# FPGA_Top.net
KiCad netlist of a schematic drawn in Altium Designer
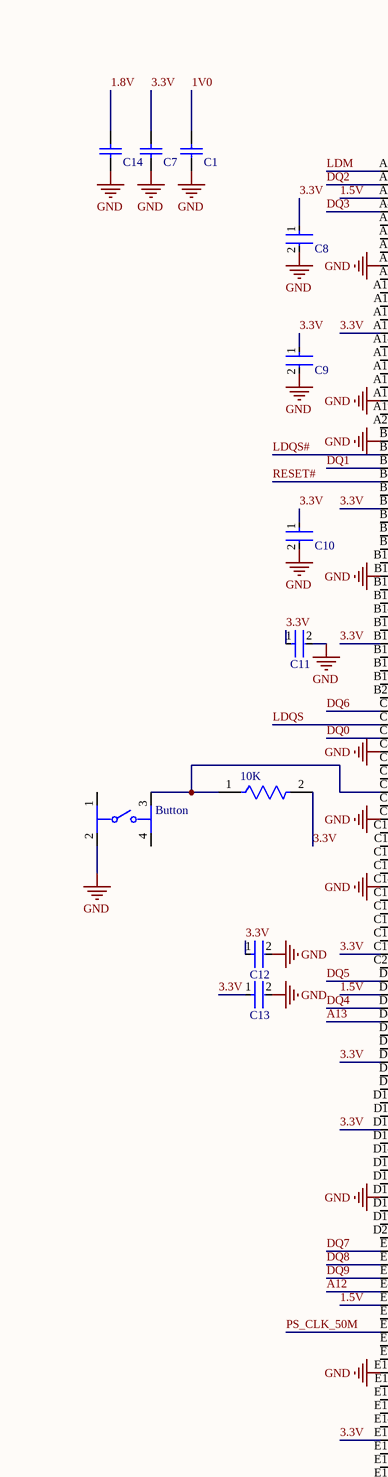
[diagram p0: FPGA_Top.SchDoc, top left]
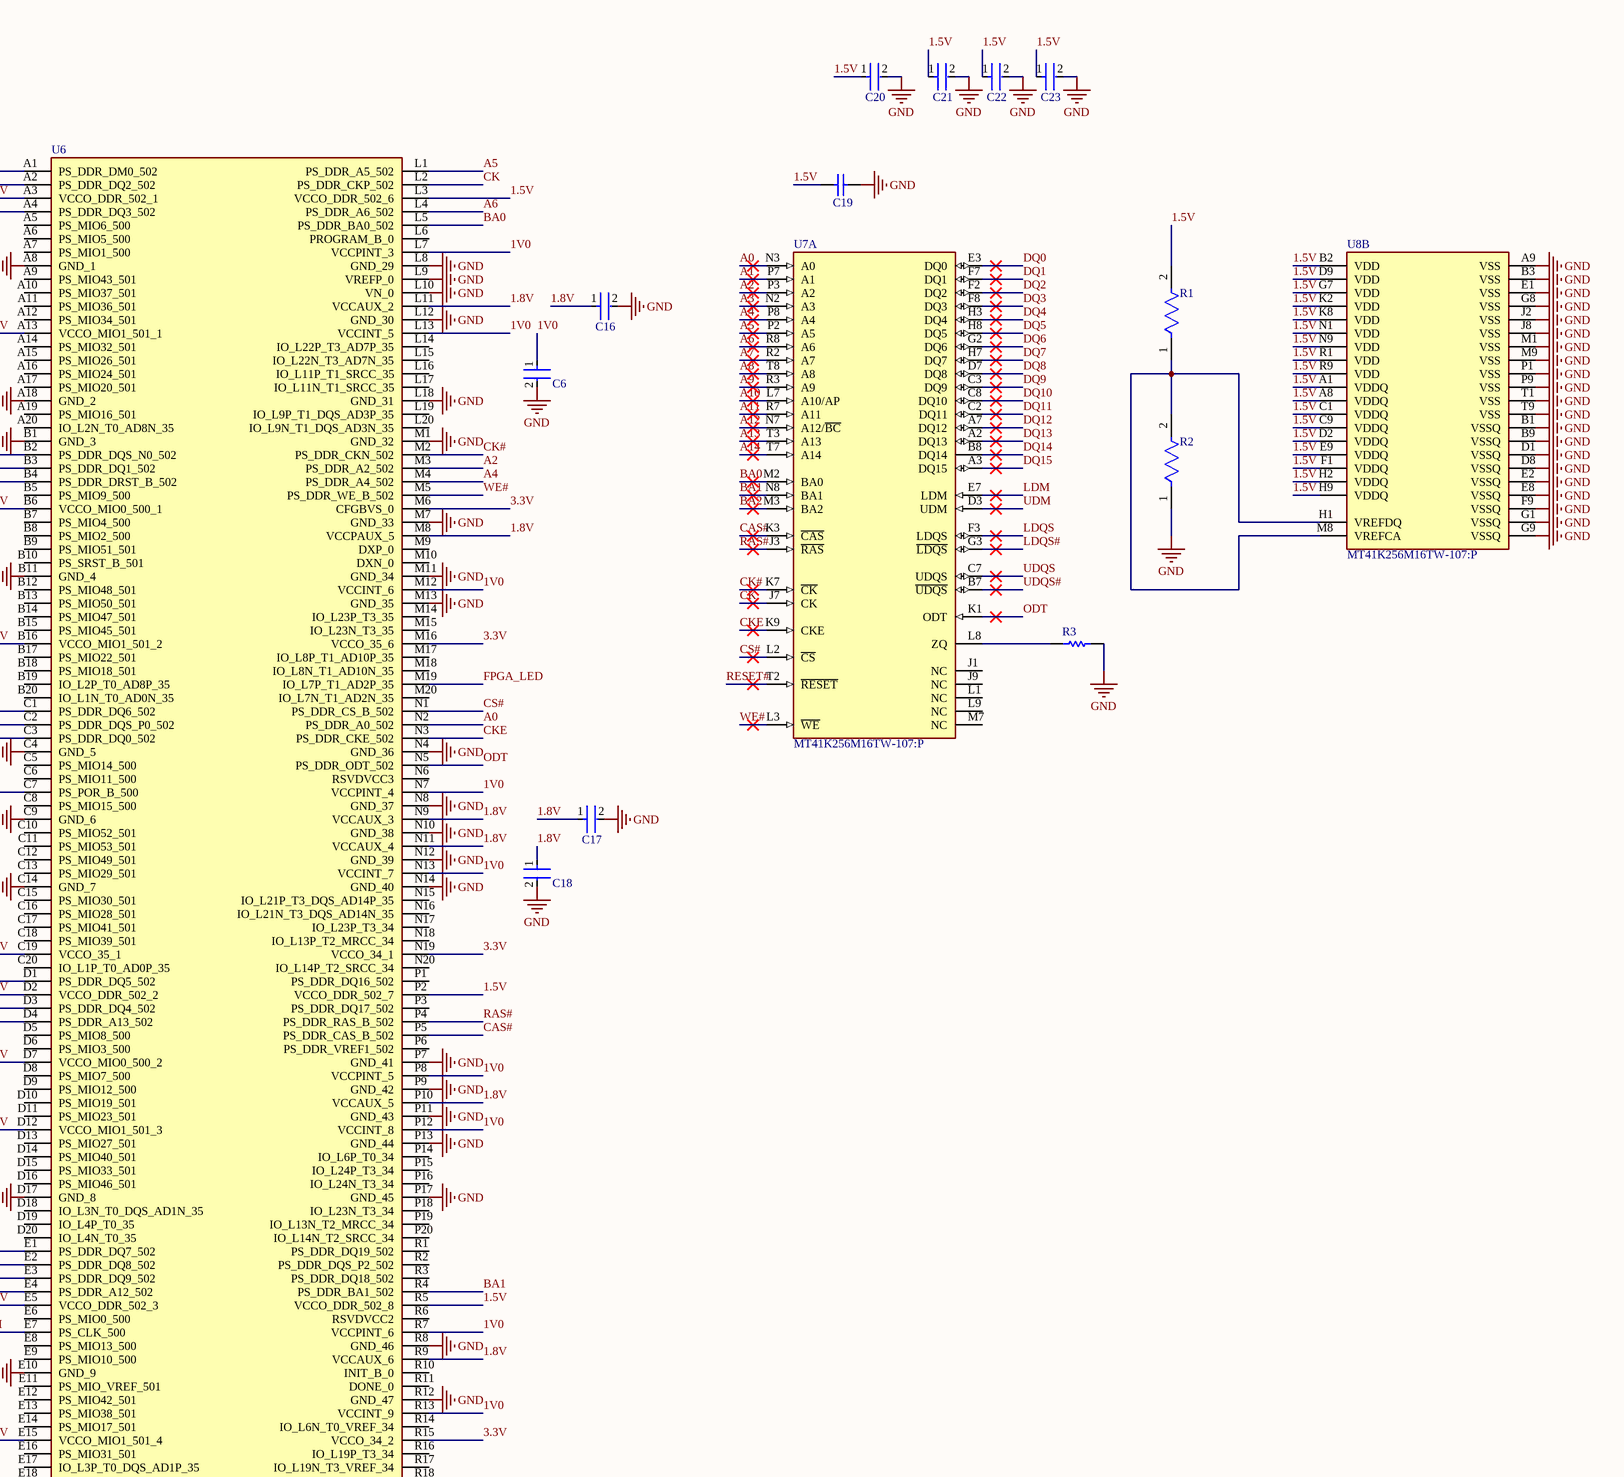
[diagram p1: FPGA_Top.SchDoc, top right]
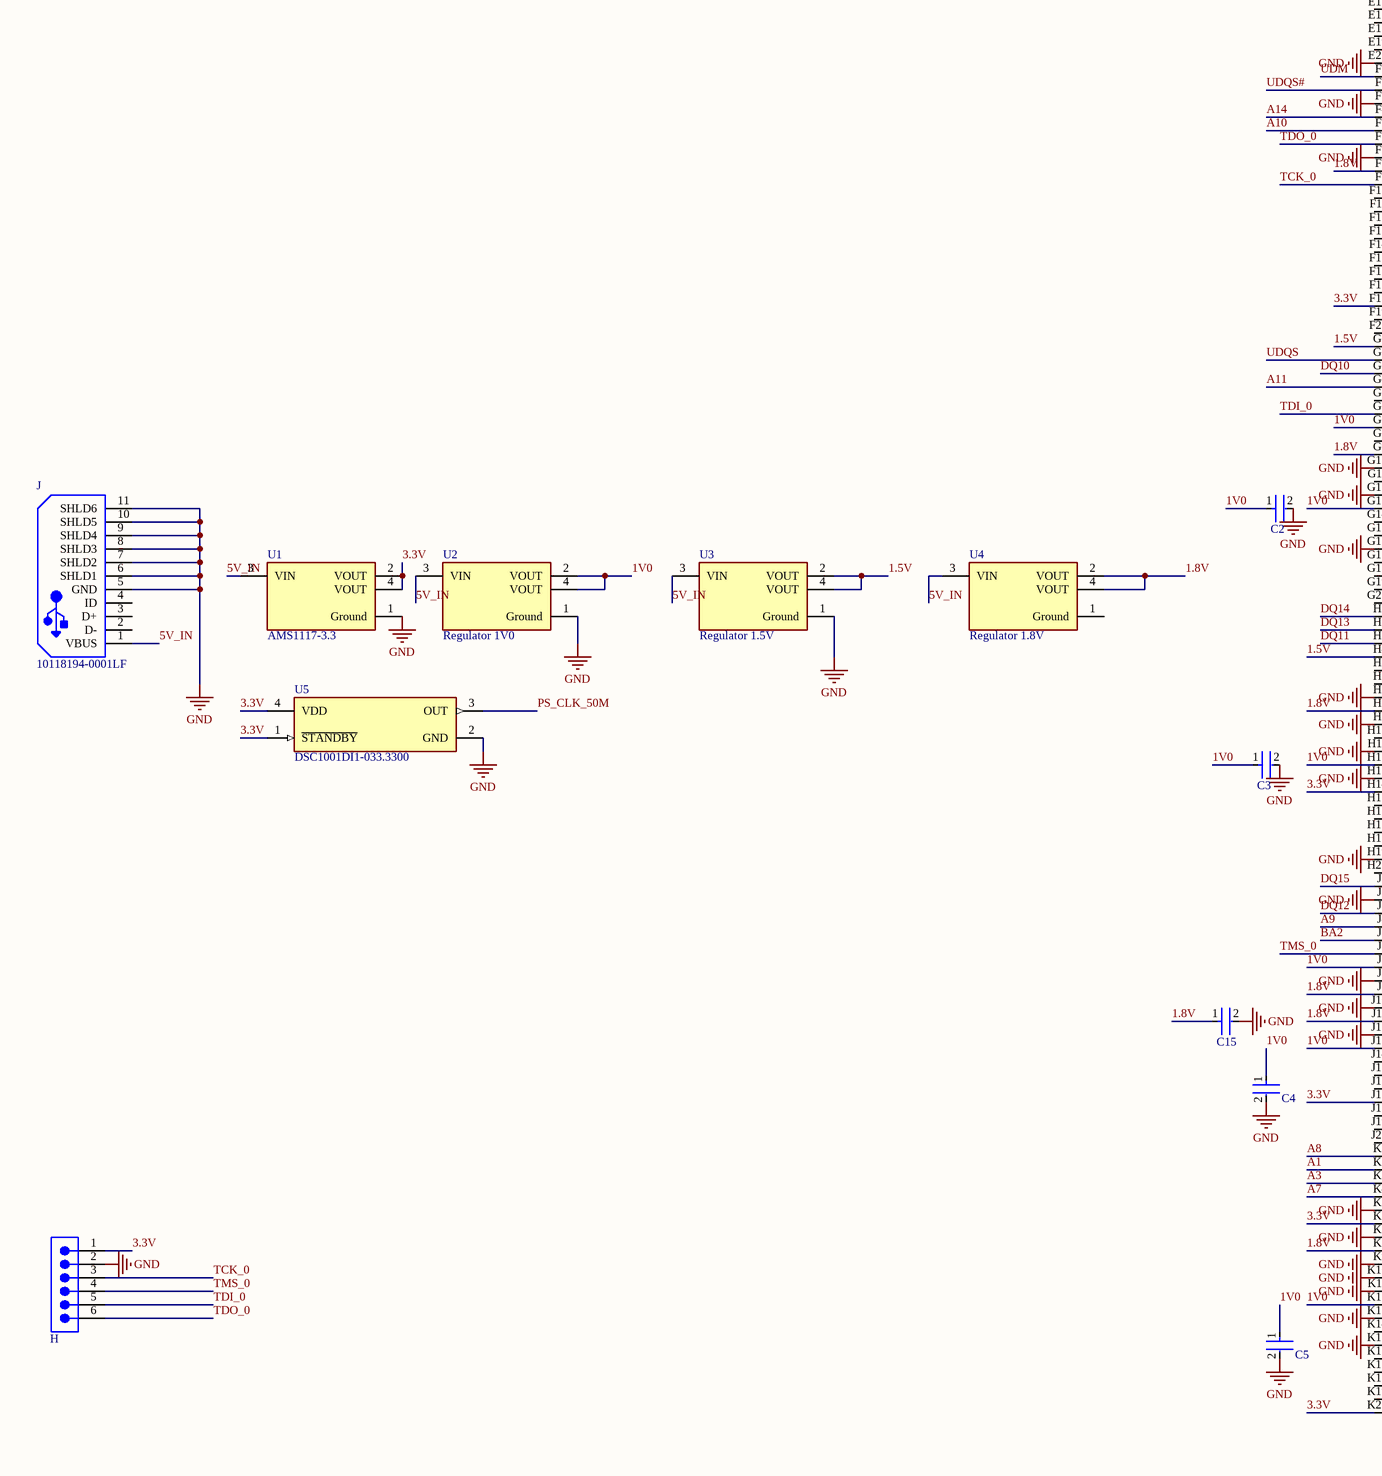
[diagram p2: FPGA_Top.SchDoc, bottom left]
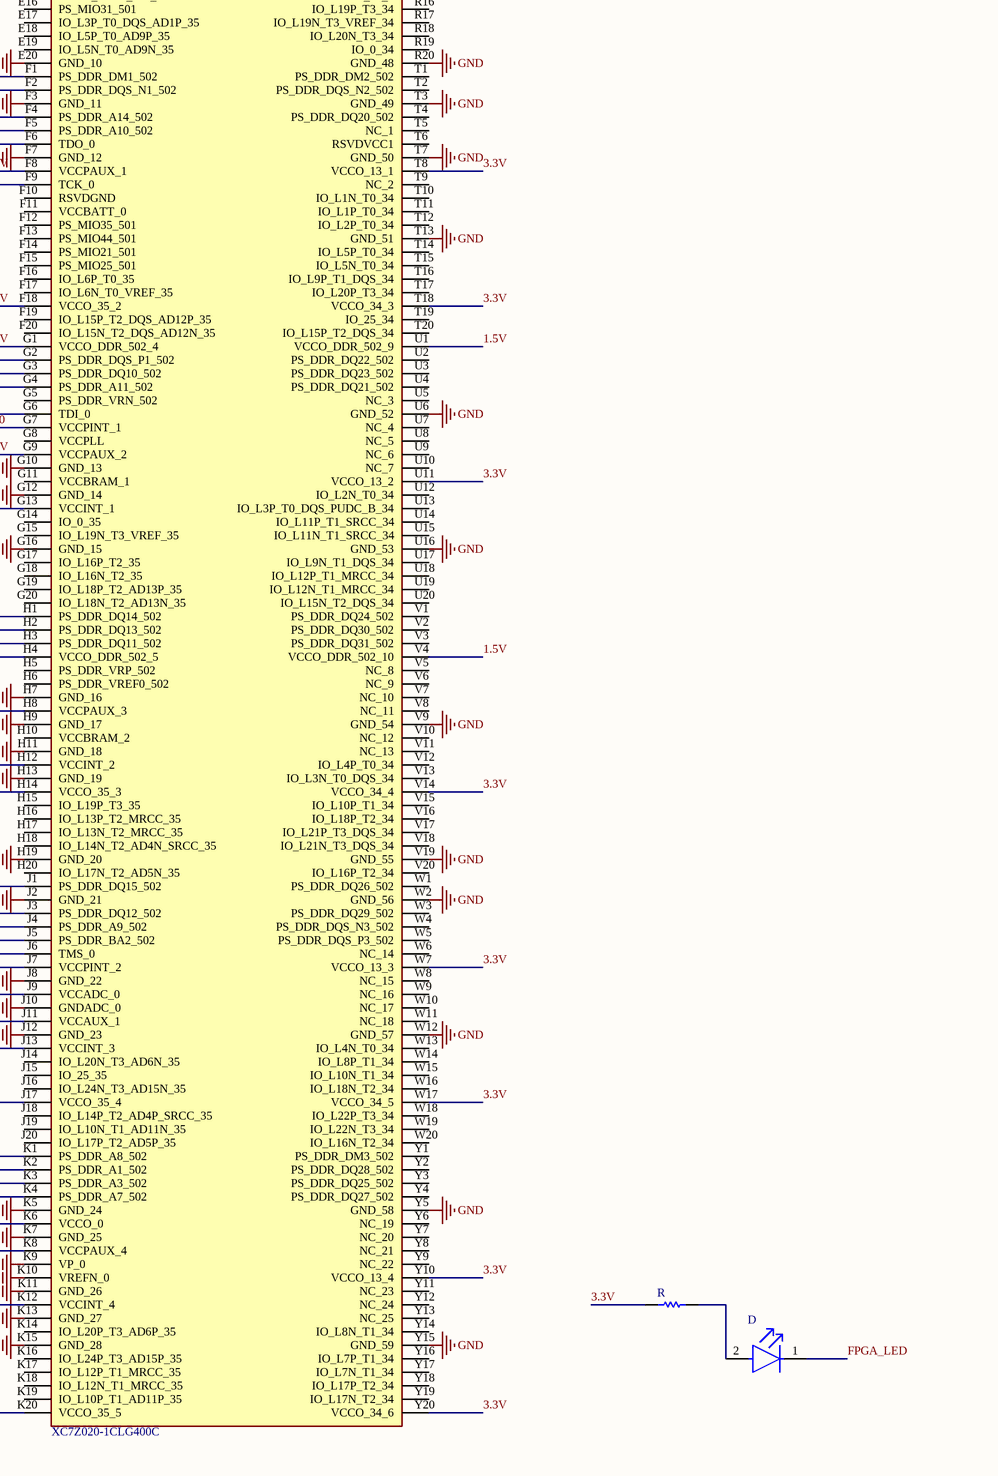
[diagram p3: FPGA_Top.SchDoc, bottom right]

(export (version "E")
  (design (tool "Eeschema 10.0.6"))
  (components
    (comp (ref "10K")
      (value "RC0402JR-0710KL")
      (footprint "FP-RC0402-0_4-IPC_C")
      (description "RES 10K OHM 5% 1/16W 0402")
      (fields (field (name "TOLERANCE") "5%"))
      (libsource (lib "Altium Content Vault") (part "1029c3af85768c4190bb7ad29bc67b5"))
    )
    (comp (ref "Button")
      (value "4-1437565-1")
      (footprint "FP-4-1437565-1-MFG")
      (description "SWITCH TACTILE SPST-NO 0.05A 24V")
      (fields
        (field (name "MANUFACTURER") "TE Connectivity")
        (field (name "OCTOPART") "https://octopart.com/fsm4jsma-te+connectivity-55488004")
      )
      (libsource (lib "Altium Content Vault") (part "b8895f3f4cefb76e1819d2863dba89b"))
    )
    (comp (ref "C1")
      (value "CL10A475KQ8NNNC")
      (footprint "CAPC1608X90X30LL10T20")
      (description "Chip Capacitor, 4.7 uF, +/- 10%, 6.3 V, -55 to 85 degC, 0603 (1608 Metric), RoHS, Tape and Reel")
      (fields (field (name "MANUFACTURER") "Samsung Electro-Mechanics"))
      (libsource (lib "Altium Content Vault") (part "CAP-NP-2"))
    )
    (comp (ref "C2")
      (value "CC0402KRX7R9BB104")
      (footprint "FP-CC0402-MFG")
      (description "CAP CER 0.1UF 50V X7R 0402")
      (fields
        (field (name "MANUFACTURER") "YAGEO")
        (field (name "OCTOPART") "https://octopart.com/cc0402krx7r9bb104-yageo-56536067")
      )
      (libsource (lib "Altium Content Vault") (part "11868f565c42a9108669ba33697ecf6"))
    )
    (comp (ref "C3")
      (value "CC0402KRX7R9BB104")
      (footprint "FP-CC0402-MFG")
      (description "CAP CER 0.1UF 50V X7R 0402")
      (fields
        (field (name "MANUFACTURER") "YAGEO")
        (field (name "OCTOPART") "https://octopart.com/cc0402krx7r9bb104-yageo-56536067")
      )
      (libsource (lib "Altium Content Vault") (part "11868f565c42a9108669ba33697ecf6"))
    )
    (comp (ref "C4")
      (value "CC0402KRX7R9BB104")
      (footprint "FP-CC0402-MFG")
      (description "CAP CER 0.1UF 50V X7R 0402")
      (fields
        (field (name "MANUFACTURER") "YAGEO")
        (field (name "OCTOPART") "https://octopart.com/cc0402krx7r9bb104-yageo-56536067")
      )
      (libsource (lib "Altium Content Vault") (part "11868f565c42a9108669ba33697ecf6"))
    )
    (comp (ref "C5")
      (value "CC0402KRX7R9BB104")
      (footprint "FP-CC0402-MFG")
      (description "CAP CER 0.1UF 50V X7R 0402")
      (fields
        (field (name "MANUFACTURER") "YAGEO")
        (field (name "OCTOPART") "https://octopart.com/cc0402krx7r9bb104-yageo-56536067")
      )
      (libsource (lib "Altium Content Vault") (part "11868f565c42a9108669ba33697ecf6"))
    )
    (comp (ref "C6")
      (value "CC0402KRX7R9BB104")
      (footprint "FP-CC0402-MFG")
      (description "CAP CER 0.1UF 50V X7R 0402")
      (fields
        (field (name "MANUFACTURER") "YAGEO")
        (field (name "OCTOPART") "https://octopart.com/cc0402krx7r9bb104-yageo-56536067")
      )
      (libsource (lib "Altium Content Vault") (part "11868f565c42a9108669ba33697ecf6"))
    )
    (comp (ref "C7")
      (value "CL10A475KQ8NNNC")
      (footprint "CAPC1608X90X30LL10T20")
      (description "Chip Capacitor, 4.7 uF, +/- 10%, 6.3 V, -55 to 85 degC, 0603 (1608 Metric), RoHS, Tape and Reel")
      (fields (field (name "MANUFACTURER") "Samsung Electro-Mechanics"))
      (libsource (lib "Altium Content Vault") (part "CAP-NP-2"))
    )
    (comp (ref "C8")
      (value "CC0402KRX7R9BB104")
      (footprint "FP-CC0402-MFG")
      (description "CAP CER 0.1UF 50V X7R 0402")
      (fields
        (field (name "MANUFACTURER") "YAGEO")
        (field (name "OCTOPART") "https://octopart.com/cc0402krx7r9bb104-yageo-56536067")
      )
      (libsource (lib "Altium Content Vault") (part "11868f565c42a9108669ba33697ecf6"))
    )
    (comp (ref "C9")
      (value "CC0402KRX7R9BB104")
      (footprint "FP-CC0402-MFG")
      (description "CAP CER 0.1UF 50V X7R 0402")
      (fields
        (field (name "MANUFACTURER") "YAGEO")
        (field (name "OCTOPART") "https://octopart.com/cc0402krx7r9bb104-yageo-56536067")
      )
      (libsource (lib "Altium Content Vault") (part "11868f565c42a9108669ba33697ecf6"))
    )
    (comp (ref "C10")
      (value "CC0402KRX7R9BB104")
      (footprint "FP-CC0402-MFG")
      (description "CAP CER 0.1UF 50V X7R 0402")
      (fields
        (field (name "MANUFACTURER") "YAGEO")
        (field (name "OCTOPART") "https://octopart.com/cc0402krx7r9bb104-yageo-56536067")
      )
      (libsource (lib "Altium Content Vault") (part "11868f565c42a9108669ba33697ecf6"))
    )
    (comp (ref "C11")
      (value "CC0402KRX7R9BB104")
      (footprint "FP-CC0402-MFG")
      (description "CAP CER 0.1UF 50V X7R 0402")
      (fields
        (field (name "MANUFACTURER") "YAGEO")
        (field (name "OCTOPART") "https://octopart.com/cc0402krx7r9bb104-yageo-56536067")
      )
      (libsource (lib "Altium Content Vault") (part "11868f565c42a9108669ba33697ecf6"))
    )
    (comp (ref "C12")
      (value "CC0402KRX7R9BB104")
      (footprint "FP-CC0402-MFG")
      (description "CAP CER 0.1UF 50V X7R 0402")
      (fields
        (field (name "MANUFACTURER") "YAGEO")
        (field (name "OCTOPART") "https://octopart.com/cc0402krx7r9bb104-yageo-56536067")
      )
      (libsource (lib "Altium Content Vault") (part "11868f565c42a9108669ba33697ecf6"))
    )
    (comp (ref "C13")
      (value "CC0402KRX7R9BB104")
      (footprint "FP-CC0402-MFG")
      (description "CAP CER 0.1UF 50V X7R 0402")
      (fields
        (field (name "MANUFACTURER") "YAGEO")
        (field (name "OCTOPART") "https://octopart.com/cc0402krx7r9bb104-yageo-56536067")
      )
      (libsource (lib "Altium Content Vault") (part "11868f565c42a9108669ba33697ecf6"))
    )
    (comp (ref "C14")
      (value "CL10A475KQ8NNNC")
      (footprint "CAPC1608X90X30LL10T20")
      (description "Chip Capacitor, 4.7 uF, +/- 10%, 6.3 V, -55 to 85 degC, 0603 (1608 Metric), RoHS, Tape and Reel")
      (fields (field (name "MANUFACTURER") "Samsung Electro-Mechanics"))
      (libsource (lib "Altium Content Vault") (part "CAP-NP-2"))
    )
    (comp (ref "C15")
      (value "CC0402KRX7R9BB104")
      (footprint "FP-CC0402-MFG")
      (description "CAP CER 0.1UF 50V X7R 0402")
      (fields
        (field (name "MANUFACTURER") "YAGEO")
        (field (name "OCTOPART") "https://octopart.com/cc0402krx7r9bb104-yageo-56536067")
      )
      (libsource (lib "Altium Content Vault") (part "11868f565c42a9108669ba33697ecf6"))
    )
    (comp (ref "C16")
      (value "CC0402KRX7R9BB104")
      (footprint "FP-CC0402-MFG")
      (description "CAP CER 0.1UF 50V X7R 0402")
      (fields
        (field (name "MANUFACTURER") "YAGEO")
        (field (name "OCTOPART") "https://octopart.com/cc0402krx7r9bb104-yageo-56536067")
      )
      (libsource (lib "Altium Content Vault") (part "11868f565c42a9108669ba33697ecf6"))
    )
    (comp (ref "C17")
      (value "CC0402KRX7R9BB104")
      (footprint "FP-CC0402-MFG")
      (description "CAP CER 0.1UF 50V X7R 0402")
      (fields
        (field (name "MANUFACTURER") "YAGEO")
        (field (name "OCTOPART") "https://octopart.com/cc0402krx7r9bb104-yageo-56536067")
      )
      (libsource (lib "Altium Content Vault") (part "11868f565c42a9108669ba33697ecf6"))
    )
    (comp (ref "C18")
      (value "CC0402KRX7R9BB104")
      (footprint "FP-CC0402-MFG")
      (description "CAP CER 0.1UF 50V X7R 0402")
      (fields
        (field (name "MANUFACTURER") "YAGEO")
        (field (name "OCTOPART") "https://octopart.com/cc0402krx7r9bb104-yageo-56536067")
      )
      (libsource (lib "Altium Content Vault") (part "11868f565c42a9108669ba33697ecf6"))
    )
    (comp (ref "C19")
      (value "CL10A475KQ8NNNC")
      (footprint "CAPC1608X90X30LL10T20")
      (description "Chip Capacitor, 4.7 uF, +/- 10%, 6.3 V, -55 to 85 degC, 0603 (1608 Metric), RoHS, Tape and Reel")
      (fields (field (name "MANUFACTURER") "Samsung Electro-Mechanics"))
      (libsource (lib "Altium Content Vault") (part "CAP-NP-2"))
    )
    (comp (ref "C20")
      (value "CC0402KRX7R9BB104")
      (footprint "FP-CC0402-MFG")
      (description "CAP CER 0.1UF 50V X7R 0402")
      (fields
        (field (name "MANUFACTURER") "YAGEO")
        (field (name "OCTOPART") "https://octopart.com/cc0402krx7r9bb104-yageo-56536067")
      )
      (libsource (lib "Altium Content Vault") (part "11868f565c42a9108669ba33697ecf6"))
    )
    (comp (ref "C21")
      (value "CC0402KRX7R9BB104")
      (footprint "FP-CC0402-MFG")
      (description "CAP CER 0.1UF 50V X7R 0402")
      (fields
        (field (name "MANUFACTURER") "YAGEO")
        (field (name "OCTOPART") "https://octopart.com/cc0402krx7r9bb104-yageo-56536067")
      )
      (libsource (lib "Altium Content Vault") (part "11868f565c42a9108669ba33697ecf6"))
    )
    (comp (ref "C22")
      (value "CC0402KRX7R9BB104")
      (footprint "FP-CC0402-MFG")
      (description "CAP CER 0.1UF 50V X7R 0402")
      (fields
        (field (name "MANUFACTURER") "YAGEO")
        (field (name "OCTOPART") "https://octopart.com/cc0402krx7r9bb104-yageo-56536067")
      )
      (libsource (lib "Altium Content Vault") (part "11868f565c42a9108669ba33697ecf6"))
    )
    (comp (ref "C23")
      (value "CC0402KRX7R9BB104")
      (footprint "FP-CC0402-MFG")
      (description "CAP CER 0.1UF 50V X7R 0402")
      (fields
        (field (name "MANUFACTURER") "YAGEO")
        (field (name "OCTOPART") "https://octopart.com/cc0402krx7r9bb104-yageo-56536067")
      )
      (libsource (lib "Altium Content Vault") (part "11868f565c42a9108669ba33697ecf6"))
    )
    (comp (ref "D")
      (value "LTST-C190KRKT")
      (footprint "FP-LTST-C190KRKT-MFG")
      (description "LED RED CLEAR CHIP SMD")
      (libsource (lib "Altium Content Vault") (part "8706943c75ba83719d021d2fdc84c58"))
    )
    (comp (ref "H")
      (value "TSW-106-07-G-S")
      (footprint "SMTC-TSW-106-07-X-S")
      (description "0.025\" SQ Post Header, Through-hole, Vertical, -55 to 125 degC, 2.54 mm Pitch, 6-Pin, Male, RoHS")
      (fields (field (name "MANUFACTURER") "Samtec"))
      (libsource (lib "Altium Content Vault") (part "SMTC-TSW-106-X-X-S-X"))
    )
    (comp (ref "J")
      (value "10118194-0001LF")
      (footprint "FCI-10118194-0001LF-5_V")
      (description "Micro USB B Type Receptacle, 1.8 A, -55 to 85 degC, 5-Pin SMD, RoHS, Tape and Reel")
      (fields (field (name "MANUFACTURER") "Amphenol FCI"))
      (libsource (lib "Altium Content Vault") (part "USB-5-6SHLD"))
    )
    (comp (ref "R")
      (value "RC0402JR-07330RL")
      (footprint "RESC1005X40X25NL05T10")
      (fields (field (name "MANUFACTURER") "Yageo / Phycomp"))
      (libsource (lib "Altium Content Vault") (part "RES"))
    )
    (comp (ref "R1")
      (value "RC0402FR-071KL")
      (footprint "FP-RC0402-0_4-IPC_A")
      (description "RES 1K OHM 1% 1/16W 0402")
      (fields (field (name "TOLERANCE") "1%"))
      (libsource (lib "Altium Content Vault") (part "1029c3af85768c4190bb7ad29bc67b5"))
    )
    (comp (ref "R2")
      (value "RC0402FR-071KL")
      (footprint "FP-RC0402-0_4-IPC_A")
      (description "RES 1K OHM 1% 1/16W 0402")
      (fields (field (name "TOLERANCE") "1%"))
      (libsource (lib "Altium Content Vault") (part "1029c3af85768c4190bb7ad29bc67b5"))
    )
    (comp (ref "R3")
      (value "240R 1% 0402(1005)")
      (footprint "RESC0402(1005)_L")
      (description "240R 0.063W 1% 0402 (1005 Metric)  SMD")
      (fields (field (name "POWER") "0.063 W") (field (name "TOLERANCE") "1 %"))
      (libsource (lib "Altium Content Vault") (part "RES"))
    )
    (comp (ref "U1")
      (value "AMS1117-3.3")
      (footprint "FP-AMS1117-IPC_C")
      (description "LDO Voltage Regulators 1A, 3.3V")
      (fields
        (field (name "OCTOPART") "https://octopart.com/ams1117-3.3-advanced+monolithic+systems-25899300")
        (field (name "MANUFACTURER") "Advanced Monolithic Systems")
      )
      (libsource (lib "Altium Content Vault") (part "8bdbb5f8e77002000e30dd2845d0354"))
    )
    (comp (ref "U2")
      (value "Regulator 1V0")
      (footprint "FP-AMS1117-IPC_C")
      (description "LDO Voltage Regulators 1A, 3.3V")
      (fields
        (field (name "MANUFACTURER PART NUMBER") "AMS1117-3.3")
        (field (name "OCTOPART") "https://octopart.com/ams1117-3.3-advanced+monolithic+systems-25899300")
      )
      (libsource (lib "Altium Content Vault") (part "8bdbb5f8e77002000e30dd2845d0354"))
    )
    (comp (ref "U3")
      (value "Regulator 1.5V")
      (footprint "FP-AMS1117-IPC_C")
      (description "LDO Voltage Regulators 1A, 3.3V")
      (fields
        (field (name "MANUFACTURER PART NUMBER") "AMS1117-3.3")
        (field (name "OCTOPART") "https://octopart.com/ams1117-3.3-advanced+monolithic+systems-25899300")
      )
      (libsource (lib "Altium Content Vault") (part "8bdbb5f8e77002000e30dd2845d0354"))
    )
    (comp (ref "U4")
      (value "Regulator 1.8V")
      (footprint "FP-AMS1117-IPC_C")
      (description "LDO Voltage Regulators 1A, 3.3V")
      (fields
        (field (name "MANUFACTURER PART NUMBER") "AMS1117-3.3")
        (field (name "OCTOPART") "https://octopart.com/ams1117-3.3-advanced+monolithic+systems-25899300")
      )
      (libsource (lib "Altium Content Vault") (part "8bdbb5f8e77002000e30dd2845d0354"))
    )
    (comp (ref "U5")
      (value "DSC1001DI1-033.3300")
      (footprint "FP-CDFN2520-4LD-PL-1-MFG")
      (description "MEMS OSC XO 33.3300MHZ CMOS SMD")
      (libsource (lib "Altium Content Vault") (part "8720c5899389794f50cb41edc4e4c8a"))
    )
    (comp (ref "U6")
      (value "XC7Z020-1CLG400C")
      (footprint "BGA400C80P20X20_1700X1700X160")
      (description "Zynq-7000 All Programmable SoC, BGA-400")
      (fields (field (name "MOUSER PART NUMBER") "217-XC7Z020-1CLG400C"))
      (libsource (lib "Altium 365 Cloud") (part "XC7Z020-1CLG400C"))
    )
    (comp (ref "U7")
      (value "MT41K256M16TW-107:P")
      (footprint "FP-TW-IPC_C")
      (description "IC DRAM 4G PARALLEL 96FBGA")
      (fields
        (field (name "MANUFACTURER") "Micron")
        (field (name "OCTOPART") "https://octopart.com/mt41k256m16tw-107%3Ap-micron-66533852")
      )
      (libsource (lib "Altium Content Vault") (part "cdaccbdf9e98e5f2804aaab7a1ea706"))
    )
    (comp (ref "U8")
      (value "MT41K256M16TW-107:P")
      (footprint "FP-TW-IPC_C")
      (description "IC DRAM 4G PARALLEL 96FBGA")
      (fields
        (field (name "MANUFACTURER") "Micron")
        (field (name "OCTOPART") "https://octopart.com/mt41k256m16tw-107%3Ap-micron-66533852")
      )
      (libsource (lib "Altium Content Vault") (part "cdaccbdf9e98e5f2804aaab7a1ea706"))
    )
  )
  (nets
    (net (code "1") (name "/1.5V") (class "Default")
      (node (ref "C19") (pin "2") (pinfunction "2_2") (pintype "passive"))
      (node (ref "C20") (pin "1") (pinfunction "1_1") (pintype "passive"))
      (node (ref "C21") (pin "1") (pinfunction "1_1") (pintype "passive"))
      (node (ref "C22") (pin "1") (pinfunction "1_1") (pintype "passive"))
      (node (ref "C23") (pin "1") (pinfunction "1_1") (pintype "passive"))
      (node (ref "R1") (pin "2") (pinfunction "2_2") (pintype "passive"))
      (node (ref "U3") (pin "2") (pinfunction "VOUT_2") (pintype "passive"))
      (node (ref "U3") (pin "4") (pinfunction "VOUT_4") (pintype "passive"))
      (node (ref "U6") (pin "A3") (pinfunction "VCCO_DDR_502_1_A3") (pintype "passive"))
      (node (ref "U6") (pin "D2") (pinfunction "VCCO_DDR_502_2_D2") (pintype "passive"))
      (node (ref "U6") (pin "E5") (pinfunction "VCCO_DDR_502_3_E5") (pintype "passive"))
      (node (ref "U6") (pin "G1") (pinfunction "VCCO_DDR_502_4_G1") (pintype "passive"))
      (node (ref "U6") (pin "H4") (pinfunction "VCCO_DDR_502_5_H4") (pintype "passive"))
      (node (ref "U6") (pin "L3") (pinfunction "VCCO_DDR_502_6_L3") (pintype "passive"))
      (node (ref "U6") (pin "P2") (pinfunction "VCCO_DDR_502_7_P2") (pintype "passive"))
      (node (ref "U6") (pin "R5") (pinfunction "VCCO_DDR_502_8_R5") (pintype "passive"))
      (node (ref "U6") (pin "U1") (pinfunction "VCCO_DDR_502_9_U1") (pintype "passive"))
      (node (ref "U6") (pin "V4") (pinfunction "VCCO_DDR_502_10_V4") (pintype "passive"))
      (node (ref "U8") (pin "A1") (pinfunction "VDDQ_A1") (pintype "power_in"))
      (node (ref "U8") (pin "A8") (pinfunction "VDDQ_A8") (pintype "power_in"))
      (node (ref "U8") (pin "B2") (pinfunction "VDD_B2") (pintype "power_in"))
      (node (ref "U8") (pin "C1") (pinfunction "VDDQ_C1") (pintype "power_in"))
      (node (ref "U8") (pin "C9") (pinfunction "VDDQ_C9") (pintype "power_in"))
      (node (ref "U8") (pin "D2") (pinfunction "VDDQ_D2") (pintype "power_in"))
      (node (ref "U8") (pin "D9") (pinfunction "VDD_D9") (pintype "power_in"))
      (node (ref "U8") (pin "E9") (pinfunction "VDDQ_E9") (pintype "power_in"))
      (node (ref "U8") (pin "F1") (pinfunction "VDDQ_F1") (pintype "power_in"))
      (node (ref "U8") (pin "G7") (pinfunction "VDD_G7") (pintype "power_in"))
      (node (ref "U8") (pin "H2") (pinfunction "VDDQ_H2") (pintype "power_in"))
      (node (ref "U8") (pin "H9") (pinfunction "VDDQ_H9") (pintype "power_in"))
      (node (ref "U8") (pin "K2") (pinfunction "VDD_K2") (pintype "power_in"))
      (node (ref "U8") (pin "K8") (pinfunction "VDD_K8") (pintype "power_in"))
      (node (ref "U8") (pin "N1") (pinfunction "VDD_N1") (pintype "power_in"))
      (node (ref "U8") (pin "N9") (pinfunction "VDD_N9") (pintype "power_in"))
      (node (ref "U8") (pin "R1") (pinfunction "VDD_R1") (pintype "power_in"))
      (node (ref "U8") (pin "R9") (pinfunction "VDD_R9") (pintype "power_in"))
    )
    (net (code "2") (name "/1.8V") (class "Default")
      (node (ref "C14") (pin "2") (pinfunction "2_2") (pintype "passive"))
      (node (ref "C15") (pin "1") (pinfunction "1_1") (pintype "passive"))
      (node (ref "C16") (pin "1") (pinfunction "1_1") (pintype "passive"))
      (node (ref "C17") (pin "1") (pinfunction "1_1") (pintype "passive"))
      (node (ref "C18") (pin "1") (pinfunction "1_1") (pintype "passive"))
      (node (ref "U4") (pin "2") (pinfunction "VOUT_2") (pintype "passive"))
      (node (ref "U4") (pin "4") (pinfunction "VOUT_4") (pintype "passive"))
      (node (ref "U6") (pin "F8") (pinfunction "VCCPAUX_1_F8") (pintype "passive"))
      (node (ref "U6") (pin "G9") (pinfunction "VCCPAUX_2_G9") (pintype "passive"))
      (node (ref "U6") (pin "H8") (pinfunction "VCCPAUX_3_H8") (pintype "passive"))
      (node (ref "U6") (pin "J11") (pinfunction "VCCAUX_1_J11") (pintype "passive"))
      (node (ref "U6") (pin "J9") (pinfunction "VCCADC_0_J9") (pintype "passive"))
      (node (ref "U6") (pin "K8") (pinfunction "VCCPAUX_4_K8") (pintype "passive"))
      (node (ref "U6") (pin "L11") (pinfunction "VCCAUX_2_L11") (pintype "passive"))
      (node (ref "U6") (pin "M8") (pinfunction "VCCPAUX_5_M8") (pintype "passive"))
      (node (ref "U6") (pin "N11") (pinfunction "VCCAUX_4_N11") (pintype "passive"))
      (node (ref "U6") (pin "N9") (pinfunction "VCCAUX_3_N9") (pintype "passive"))
      (node (ref "U6") (pin "P10") (pinfunction "VCCAUX_5_P10") (pintype "passive"))
      (node (ref "U6") (pin "R9") (pinfunction "VCCAUX_6_R9") (pintype "passive"))
    )
    (net (code "3") (name "/1V0") (class "Default")
      (node (ref "C1") (pin "2") (pinfunction "2_2") (pintype "passive"))
      (node (ref "C2") (pin "1") (pinfunction "1_1") (pintype "passive"))
      (node (ref "C3") (pin "1") (pinfunction "1_1") (pintype "passive"))
      (node (ref "C4") (pin "1") (pinfunction "1_1") (pintype "passive"))
      (node (ref "C5") (pin "1") (pinfunction "1_1") (pintype "passive"))
      (node (ref "C6") (pin "1") (pinfunction "1_1") (pintype "passive"))
      (node (ref "U2") (pin "2") (pinfunction "VOUT_2") (pintype "passive"))
      (node (ref "U2") (pin "4") (pinfunction "VOUT_4") (pintype "passive"))
      (node (ref "U6") (pin "G13") (pinfunction "VCCINT_1_G13") (pintype "passive"))
      (node (ref "U6") (pin "G7") (pinfunction "VCCPINT_1_G7") (pintype "passive"))
      (node (ref "U6") (pin "H12") (pinfunction "VCCINT_2_H12") (pintype "passive"))
      (node (ref "U6") (pin "J13") (pinfunction "VCCINT_3_J13") (pintype "passive"))
      (node (ref "U6") (pin "J7") (pinfunction "VCCPINT_2_J7") (pintype "passive"))
      (node (ref "U6") (pin "K12") (pinfunction "VCCINT_4_K12") (pintype "passive"))
      (node (ref "U6") (pin "L13") (pinfunction "VCCINT_5_L13") (pintype "passive"))
      (node (ref "U6") (pin "L7") (pinfunction "VCCPINT_3_L7") (pintype "passive"))
      (node (ref "U6") (pin "M12") (pinfunction "VCCINT_6_M12") (pintype "passive"))
      (node (ref "U6") (pin "N13") (pinfunction "VCCINT_7_N13") (pintype "passive"))
      (node (ref "U6") (pin "N7") (pinfunction "VCCPINT_4_N7") (pintype "passive"))
      (node (ref "U6") (pin "P12") (pinfunction "VCCINT_8_P12") (pintype "passive"))
      (node (ref "U6") (pin "P8") (pinfunction "VCCPINT_5_P8") (pintype "passive"))
      (node (ref "U6") (pin "R13") (pinfunction "VCCINT_9_R13") (pintype "passive"))
      (node (ref "U6") (pin "R7") (pinfunction "VCCPINT_6_R7") (pintype "passive"))
    )
    (net (code "4") (name "/3.3V") (class "Default")
      (node (ref "10K") (pin "2") (pinfunction "2_2") (pintype "passive"))
      (node (ref "C10") (pin "1") (pinfunction "1_1") (pintype "passive"))
      (node (ref "C11") (pin "1") (pinfunction "1_1") (pintype "passive"))
      (node (ref "C12") (pin "1") (pinfunction "1_1") (pintype "passive"))
      (node (ref "C13") (pin "1") (pinfunction "1_1") (pintype "passive"))
      (node (ref "C7") (pin "2") (pinfunction "2_2") (pintype "passive"))
      (node (ref "C8") (pin "1") (pinfunction "1_1") (pintype "passive"))
      (node (ref "C9") (pin "1") (pinfunction "1_1") (pintype "passive"))
      (node (ref "H") (pin "1") (pinfunction "1_1") (pintype "passive"))
      (node (ref "R") (pin "1") (pinfunction "1_1") (pintype "passive"))
      (node (ref "U1") (pin "2") (pinfunction "VOUT_2") (pintype "passive"))
      (node (ref "U1") (pin "4") (pinfunction "VOUT_4") (pintype "passive"))
      (node (ref "U5") (pin "1") (pinfunction "~{STANDBY}_1") (pintype "input"))
      (node (ref "U5") (pin "4") (pinfunction "VDD_4") (pintype "power_in"))
      (node (ref "U6") (pin "A13") (pinfunction "VCCO_MIO1_501_1_A13") (pintype "passive"))
      (node (ref "U6") (pin "B16") (pinfunction "VCCO_MIO1_501_2_B16") (pintype "passive"))
      (node (ref "U6") (pin "B6") (pinfunction "VCCO_MIO0_500_1_B6") (pintype "passive"))
      (node (ref "U6") (pin "C19") (pinfunction "VCCO_35_1_C19") (pintype "passive"))
      (node (ref "U6") (pin "D12") (pinfunction "VCCO_MIO1_501_3_D12") (pintype "passive"))
      (node (ref "U6") (pin "D7") (pinfunction "VCCO_MIO0_500_2_D7") (pintype "passive"))
      (node (ref "U6") (pin "E15") (pinfunction "VCCO_MIO1_501_4_E15") (pintype "passive"))
      (node (ref "U6") (pin "F18") (pinfunction "VCCO_35_2_F18") (pintype "passive"))
      (node (ref "U6") (pin "H14") (pinfunction "VCCO_35_3_H14") (pintype "passive"))
      (node (ref "U6") (pin "J17") (pinfunction "VCCO_35_4_J17") (pintype "passive"))
      (node (ref "U6") (pin "K20") (pinfunction "VCCO_35_5_K20") (pintype "passive"))
      (node (ref "U6") (pin "K6") (pinfunction "VCCO_0_K6") (pintype "passive"))
      (node (ref "U6") (pin "M16") (pinfunction "VCCO_35_6_M16") (pintype "passive"))
      (node (ref "U6") (pin "M6") (pinfunction "CFGBVS_0_M6") (pintype "passive"))
      (node (ref "U6") (pin "N19") (pinfunction "VCCO_34_1_N19") (pintype "passive"))
      (node (ref "U6") (pin "R15") (pinfunction "VCCO_34_2_R15") (pintype "passive"))
      (node (ref "U6") (pin "T18") (pinfunction "VCCO_34_3_T18") (pintype "passive"))
      (node (ref "U6") (pin "T8") (pinfunction "VCCO_13_1_T8") (pintype "passive"))
      (node (ref "U6") (pin "U11") (pinfunction "VCCO_13_2_U11") (pintype "passive"))
      (node (ref "U6") (pin "V14") (pinfunction "VCCO_34_4_V14") (pintype "passive"))
      (node (ref "U6") (pin "W17") (pinfunction "VCCO_34_5_W17") (pintype "passive"))
      (node (ref "U6") (pin "W7") (pinfunction "VCCO_13_3_W7") (pintype "passive"))
      (node (ref "U6") (pin "Y10") (pinfunction "VCCO_13_4_Y10") (pintype "passive"))
      (node (ref "U6") (pin "Y20") (pinfunction "VCCO_34_6_Y20") (pintype "passive"))
    )
    (net (code "5") (name "/5V_IN") (class "Default")
      (node (ref "J") (pin "1") (pinfunction "VBUS_1") (pintype "passive"))
      (node (ref "U1") (pin "3") (pinfunction "VIN_3") (pintype "power_in"))
      (node (ref "U2") (pin "3") (pinfunction "VIN_3") (pintype "power_in"))
      (node (ref "U3") (pin "3") (pinfunction "VIN_3") (pintype "power_in"))
      (node (ref "U4") (pin "3") (pinfunction "VIN_3") (pintype "power_in"))
    )
    (net (code "6") (name "/A0") (class "Default")
      (node (ref "U6") (pin "N2") (pinfunction "PS_DDR_A0_502_N2") (pintype "passive"))
      (node (ref "U7") (pin "N3") (pinfunction "A0_N3") (pintype "input"))
    )
    (net (code "7") (name "/A1") (class "Default")
      (node (ref "U6") (pin "K2") (pinfunction "PS_DDR_A1_502_K2") (pintype "passive"))
      (node (ref "U7") (pin "P7") (pinfunction "A1_P7") (pintype "input"))
    )
    (net (code "8") (name "/A2") (class "Default")
      (node (ref "U6") (pin "M3") (pinfunction "PS_DDR_A2_502_M3") (pintype "passive"))
      (node (ref "U7") (pin "P3") (pinfunction "A2_P3") (pintype "input"))
    )
    (net (code "9") (name "/A3") (class "Default")
      (node (ref "U6") (pin "K3") (pinfunction "PS_DDR_A3_502_K3") (pintype "passive"))
      (node (ref "U7") (pin "N2") (pinfunction "A3_N2") (pintype "input"))
    )
    (net (code "10") (name "/A4") (class "Default")
      (node (ref "U6") (pin "M4") (pinfunction "PS_DDR_A4_502_M4") (pintype "passive"))
      (node (ref "U7") (pin "P8") (pinfunction "A4_P8") (pintype "input"))
    )
    (net (code "11") (name "/A5") (class "Default")
      (node (ref "U6") (pin "L1") (pinfunction "PS_DDR_A5_502_L1") (pintype "passive"))
      (node (ref "U7") (pin "P2") (pinfunction "A5_P2") (pintype "input"))
    )
    (net (code "12") (name "/A6") (class "Default")
      (node (ref "U6") (pin "L4") (pinfunction "PS_DDR_A6_502_L4") (pintype "passive"))
      (node (ref "U7") (pin "R8") (pinfunction "A6_R8") (pintype "input"))
    )
    (net (code "13") (name "/A7") (class "Default")
      (node (ref "U6") (pin "K4") (pinfunction "PS_DDR_A7_502_K4") (pintype "passive"))
      (node (ref "U7") (pin "R2") (pinfunction "A7_R2") (pintype "input"))
    )
    (net (code "14") (name "/A8") (class "Default")
      (node (ref "U6") (pin "K1") (pinfunction "PS_DDR_A8_502_K1") (pintype "passive"))
      (node (ref "U7") (pin "T8") (pinfunction "A8_T8") (pintype "input"))
    )
    (net (code "15") (name "/A9") (class "Default")
      (node (ref "U6") (pin "J4") (pinfunction "PS_DDR_A9_502_J4") (pintype "passive"))
      (node (ref "U7") (pin "R3") (pinfunction "A9_R3") (pintype "input"))
    )
    (net (code "16") (name "/A10") (class "Default")
      (node (ref "U6") (pin "F5") (pinfunction "PS_DDR_A10_502_F5") (pintype "passive"))
      (node (ref "U7") (pin "L7") (pinfunction "A10/AP_L7") (pintype "input"))
    )
    (net (code "17") (name "/A11") (class "Default")
      (node (ref "U6") (pin "G4") (pinfunction "PS_DDR_A11_502_G4") (pintype "passive"))
      (node (ref "U7") (pin "R7") (pinfunction "A11_R7") (pintype "input"))
    )
    (net (code "18") (name "/A12") (class "Default")
      (node (ref "U6") (pin "E4") (pinfunction "PS_DDR_A12_502_E4") (pintype "passive"))
      (node (ref "U7") (pin "N7") (pinfunction "A12/~{BC}_N7") (pintype "input"))
    )
    (net (code "19") (name "/A13") (class "Default")
      (node (ref "U6") (pin "D4") (pinfunction "PS_DDR_A13_502_D4") (pintype "passive"))
      (node (ref "U7") (pin "T3") (pinfunction "A13_T3") (pintype "input"))
    )
    (net (code "20") (name "/A14") (class "Default")
      (node (ref "U6") (pin "F4") (pinfunction "PS_DDR_A14_502_F4") (pintype "passive"))
      (node (ref "U7") (pin "T7") (pinfunction "A14_T7") (pintype "input"))
    )
    (net (code "21") (name "/BA0") (class "Default")
      (node (ref "U6") (pin "L5") (pinfunction "PS_DDR_BA0_502_L5") (pintype "passive"))
      (node (ref "U7") (pin "M2") (pinfunction "BA0_M2") (pintype "input"))
    )
    (net (code "22") (name "/BA1") (class "Default")
      (node (ref "U6") (pin "R4") (pinfunction "PS_DDR_BA1_502_R4") (pintype "passive"))
      (node (ref "U7") (pin "N8") (pinfunction "BA1_N8") (pintype "input"))
    )
    (net (code "23") (name "/BA2") (class "Default")
      (node (ref "U6") (pin "J5") (pinfunction "PS_DDR_BA2_502_J5") (pintype "passive"))
      (node (ref "U7") (pin "M3") (pinfunction "BA2_M3") (pintype "input"))
    )
    (net (code "24") (name "/CAS#") (class "Default")
      (node (ref "U6") (pin "P5") (pinfunction "PS_DDR_CAS_B_502_P5") (pintype "passive"))
      (node (ref "U7") (pin "K3") (pinfunction "~{CAS}_K3") (pintype "input"))
    )
    (net (code "25") (name "/CK") (class "Default")
      (node (ref "U6") (pin "L2") (pinfunction "PS_DDR_CKP_502_L2") (pintype "passive"))
      (node (ref "U7") (pin "J7") (pinfunction "CK_J7") (pintype "input"))
    )
    (net (code "26") (name "/CK#") (class "Default")
      (node (ref "U6") (pin "M2") (pinfunction "PS_DDR_CKN_502_M2") (pintype "passive"))
      (node (ref "U7") (pin "K7") (pinfunction "~{CK}_K7") (pintype "input"))
    )
    (net (code "27") (name "/CKE") (class "Default")
      (node (ref "U6") (pin "N3") (pinfunction "PS_DDR_CKE_502_N3") (pintype "passive"))
      (node (ref "U7") (pin "K9") (pinfunction "CKE_K9") (pintype "input"))
    )
    (net (code "28") (name "/CS#") (class "Default")
      (node (ref "U6") (pin "N1") (pinfunction "PS_DDR_CS_B_502_N1") (pintype "passive"))
      (node (ref "U7") (pin "L2") (pinfunction "~{CS}_L2") (pintype "input"))
    )
    (net (code "29") (name "/DQ0") (class "Default")
      (node (ref "U6") (pin "C3") (pinfunction "PS_DDR_DQ0_502_C3") (pintype "passive"))
      (node (ref "U7") (pin "E3") (pinfunction "DQ0_E3") (pintype "bidirectional"))
    )
    (net (code "30") (name "/DQ1") (class "Default")
      (node (ref "U6") (pin "B3") (pinfunction "PS_DDR_DQ1_502_B3") (pintype "passive"))
      (node (ref "U7") (pin "F7") (pinfunction "DQ1_F7") (pintype "bidirectional"))
    )
    (net (code "31") (name "/DQ2") (class "Default")
      (node (ref "U6") (pin "A2") (pinfunction "PS_DDR_DQ2_502_A2") (pintype "passive"))
      (node (ref "U7") (pin "F2") (pinfunction "DQ2_F2") (pintype "bidirectional"))
    )
    (net (code "32") (name "/DQ3") (class "Default")
      (node (ref "U6") (pin "A4") (pinfunction "PS_DDR_DQ3_502_A4") (pintype "passive"))
      (node (ref "U7") (pin "F8") (pinfunction "DQ3_F8") (pintype "bidirectional"))
    )
    (net (code "33") (name "/DQ4") (class "Default")
      (node (ref "U6") (pin "D3") (pinfunction "PS_DDR_DQ4_502_D3") (pintype "passive"))
      (node (ref "U7") (pin "H3") (pinfunction "DQ4_H3") (pintype "bidirectional"))
    )
    (net (code "34") (name "/DQ5") (class "Default")
      (node (ref "U6") (pin "D1") (pinfunction "PS_DDR_DQ5_502_D1") (pintype "passive"))
      (node (ref "U7") (pin "H8") (pinfunction "DQ5_H8") (pintype "bidirectional"))
    )
    (net (code "35") (name "/DQ6") (class "Default")
      (node (ref "U6") (pin "C1") (pinfunction "PS_DDR_DQ6_502_C1") (pintype "passive"))
      (node (ref "U7") (pin "G2") (pinfunction "DQ6_G2") (pintype "bidirectional"))
    )
    (net (code "36") (name "/DQ7") (class "Default")
      (node (ref "U6") (pin "E1") (pinfunction "PS_DDR_DQ7_502_E1") (pintype "passive"))
      (node (ref "U7") (pin "H7") (pinfunction "DQ7_H7") (pintype "bidirectional"))
    )
    (net (code "37") (name "/DQ8") (class "Default")
      (node (ref "U6") (pin "E2") (pinfunction "PS_DDR_DQ8_502_E2") (pintype "passive"))
      (node (ref "U7") (pin "D7") (pinfunction "DQ8_D7") (pintype "bidirectional"))
    )
    (net (code "38") (name "/DQ9") (class "Default")
      (node (ref "U6") (pin "E3") (pinfunction "PS_DDR_DQ9_502_E3") (pintype "passive"))
      (node (ref "U7") (pin "C3") (pinfunction "DQ9_C3") (pintype "bidirectional"))
    )
    (net (code "39") (name "/DQ10") (class "Default")
      (node (ref "U6") (pin "G3") (pinfunction "PS_DDR_DQ10_502_G3") (pintype "passive"))
      (node (ref "U7") (pin "C8") (pinfunction "DQ10_C8") (pintype "bidirectional"))
    )
    (net (code "40") (name "/DQ11") (class "Default")
      (node (ref "U6") (pin "H3") (pinfunction "PS_DDR_DQ11_502_H3") (pintype "passive"))
      (node (ref "U7") (pin "C2") (pinfunction "DQ11_C2") (pintype "bidirectional"))
    )
    (net (code "41") (name "/DQ12") (class "Default")
      (node (ref "U6") (pin "J3") (pinfunction "PS_DDR_DQ12_502_J3") (pintype "passive"))
      (node (ref "U7") (pin "A7") (pinfunction "DQ12_A7") (pintype "bidirectional"))
    )
    (net (code "42") (name "/DQ13") (class "Default")
      (node (ref "U6") (pin "H2") (pinfunction "PS_DDR_DQ13_502_H2") (pintype "passive"))
      (node (ref "U7") (pin "A2") (pinfunction "DQ13_A2") (pintype "bidirectional"))
    )
    (net (code "43") (name "/DQ14") (class "Default")
      (node (ref "U6") (pin "H1") (pinfunction "PS_DDR_DQ14_502_H1") (pintype "passive"))
      (node (ref "U7") (pin "B8") (pinfunction "DQ14_B8") (pintype "power_in"))
    )
    (net (code "44") (name "/DQ15") (class "Default")
      (node (ref "U6") (pin "J1") (pinfunction "PS_DDR_DQ15_502_J1") (pintype "passive"))
      (node (ref "U7") (pin "A3") (pinfunction "DQ15_A3") (pintype "bidirectional"))
    )
    (net (code "45") (name "/FPGA_LED") (class "Default")
      (node (ref "D") (pin "1") (pinfunction "C_1") (pintype "passive"))
      (node (ref "U6") (pin "M19") (pinfunction "IO_L7P_T1_AD2P_35_M19") (pintype "passive"))
    )
    (net (code "46") (name "/LDM") (class "Default")
      (node (ref "U6") (pin "A1") (pinfunction "PS_DDR_DM0_502_A1") (pintype "passive"))
      (node (ref "U7") (pin "E7") (pinfunction "LDM_E7") (pintype "input"))
    )
    (net (code "47") (name "/LDQS") (class "Default")
      (node (ref "U6") (pin "C2") (pinfunction "PS_DDR_DQS_P0_502_C2") (pintype "passive"))
      (node (ref "U7") (pin "F3") (pinfunction "LDQS_F3") (pintype "bidirectional"))
    )
    (net (code "48") (name "/LDQS#") (class "Default")
      (node (ref "U6") (pin "B2") (pinfunction "PS_DDR_DQS_N0_502_B2") (pintype "passive"))
      (node (ref "U7") (pin "G3") (pinfunction "~{LDQS}_G3") (pintype "bidirectional"))
    )
    (net (code "49") (name "/ODT") (class "Default")
      (node (ref "U6") (pin "N5") (pinfunction "PS_DDR_ODT_502_N5") (pintype "passive"))
      (node (ref "U7") (pin "K1") (pinfunction "ODT_K1") (pintype "input"))
    )
    (net (code "50") (name "/PS_CLK_50M") (class "Default")
      (node (ref "U5") (pin "3") (pinfunction "OUT_3") (pintype "output"))
      (node (ref "U6") (pin "E7") (pinfunction "PS_CLK_500_E7") (pintype "passive"))
    )
    (net (code "51") (name "/RAS#") (class "Default")
      (node (ref "U6") (pin "P4") (pinfunction "PS_DDR_RAS_B_502_P4") (pintype "passive"))
      (node (ref "U7") (pin "J3") (pinfunction "~{RAS}_J3") (pintype "input"))
    )
    (net (code "52") (name "/RESET#") (class "Default")
      (node (ref "U6") (pin "B4") (pinfunction "PS_DDR_DRST_B_502_B4") (pintype "passive"))
      (node (ref "U7") (pin "T2") (pinfunction "~{RESET}_T2") (pintype "input"))
    )
    (net (code "53") (name "/TCK_0") (class "Default")
      (node (ref "H") (pin "3") (pinfunction "3_3") (pintype "passive"))
      (node (ref "U6") (pin "F9") (pinfunction "TCK_0_F9") (pintype "passive"))
    )
    (net (code "54") (name "/TDI_0") (class "Default")
      (node (ref "H") (pin "5") (pinfunction "5_5") (pintype "passive"))
      (node (ref "U6") (pin "G6") (pinfunction "TDI_0_G6") (pintype "passive"))
    )
    (net (code "55") (name "/TDO_0") (class "Default")
      (node (ref "H") (pin "6") (pinfunction "6_6") (pintype "passive"))
      (node (ref "U6") (pin "F6") (pinfunction "TDO_0_F6") (pintype "passive"))
    )
    (net (code "56") (name "/TMS_0") (class "Default")
      (node (ref "H") (pin "4") (pinfunction "4_4") (pintype "passive"))
      (node (ref "U6") (pin "J6") (pinfunction "TMS_0_J6") (pintype "passive"))
    )
    (net (code "57") (name "/UDM") (class "Default")
      (node (ref "U6") (pin "F1") (pinfunction "PS_DDR_DM1_502_F1") (pintype "passive"))
      (node (ref "U7") (pin "D3") (pinfunction "UDM_D3") (pintype "input"))
    )
    (net (code "58") (name "/UDQS") (class "Default")
      (node (ref "U6") (pin "G2") (pinfunction "PS_DDR_DQS_P1_502_G2") (pintype "passive"))
      (node (ref "U7") (pin "C7") (pinfunction "UDQS_C7") (pintype "bidirectional"))
    )
    (net (code "59") (name "/UDQS#") (class "Default")
      (node (ref "U6") (pin "F2") (pinfunction "PS_DDR_DQS_N1_502_F2") (pintype "passive"))
      (node (ref "U7") (pin "B7") (pinfunction "~{UDQS}_B7") (pintype "bidirectional"))
    )
    (net (code "60") (name "/WE#") (class "Default")
      (node (ref "U6") (pin "M5") (pinfunction "PS_DDR_WE_B_502_M5") (pintype "passive"))
      (node (ref "U7") (pin "L3") (pinfunction "~{WE}_L3") (pintype "input"))
    )
    (net (code "61") (name "GND") (class "Default")
      (node (ref "Button") (pin "2") (pinfunction "2_2") (pintype "passive"))
      (node (ref "C1") (pin "1") (pinfunction "1_1") (pintype "passive"))
      (node (ref "C10") (pin "2") (pinfunction "2_2") (pintype "passive"))
      (node (ref "C11") (pin "2") (pinfunction "2_2") (pintype "passive"))
      (node (ref "C12") (pin "2") (pinfunction "2_2") (pintype "passive"))
      (node (ref "C13") (pin "2") (pinfunction "2_2") (pintype "passive"))
      (node (ref "C14") (pin "1") (pinfunction "1_1") (pintype "passive"))
      (node (ref "C15") (pin "2") (pinfunction "2_2") (pintype "passive"))
      (node (ref "C16") (pin "2") (pinfunction "2_2") (pintype "passive"))
      (node (ref "C17") (pin "2") (pinfunction "2_2") (pintype "passive"))
      (node (ref "C18") (pin "2") (pinfunction "2_2") (pintype "passive"))
      (node (ref "C19") (pin "1") (pinfunction "1_1") (pintype "passive"))
      (node (ref "C2") (pin "2") (pinfunction "2_2") (pintype "passive"))
      (node (ref "C20") (pin "2") (pinfunction "2_2") (pintype "passive"))
      (node (ref "C21") (pin "2") (pinfunction "2_2") (pintype "passive"))
      (node (ref "C22") (pin "2") (pinfunction "2_2") (pintype "passive"))
      (node (ref "C23") (pin "2") (pinfunction "2_2") (pintype "passive"))
      (node (ref "C3") (pin "2") (pinfunction "2_2") (pintype "passive"))
      (node (ref "C4") (pin "2") (pinfunction "2_2") (pintype "passive"))
      (node (ref "C5") (pin "2") (pinfunction "2_2") (pintype "passive"))
      (node (ref "C6") (pin "2") (pinfunction "2_2") (pintype "passive"))
      (node (ref "C7") (pin "1") (pinfunction "1_1") (pintype "passive"))
      (node (ref "C8") (pin "2") (pinfunction "2_2") (pintype "passive"))
      (node (ref "C9") (pin "2") (pinfunction "2_2") (pintype "passive"))
      (node (ref "H") (pin "2") (pinfunction "2_2") (pintype "passive"))
      (node (ref "J") (pin "10") (pinfunction "SHLD5_10") (pintype "passive"))
      (node (ref "J") (pin "11") (pinfunction "SHLD6_11") (pintype "passive"))
      (node (ref "J") (pin "5") (pinfunction "GND_5") (pintype "passive"))
      (node (ref "J") (pin "6") (pinfunction "SHLD1_6") (pintype "passive"))
      (node (ref "J") (pin "7") (pinfunction "SHLD2_7") (pintype "passive"))
      (node (ref "J") (pin "8") (pinfunction "SHLD3_8") (pintype "passive"))
      (node (ref "J") (pin "9") (pinfunction "SHLD4_9") (pintype "passive"))
      (node (ref "R2") (pin "1") (pinfunction "1_1") (pintype "passive"))
      (node (ref "R3") (pin "2") (pinfunction "2_2") (pintype "passive"))
      (node (ref "U1") (pin "1") (pinfunction "Ground_1") (pintype "power_in"))
      (node (ref "U2") (pin "1") (pinfunction "Ground_1") (pintype "power_in"))
      (node (ref "U3") (pin "1") (pinfunction "Ground_1") (pintype "power_in"))
      (node (ref "U5") (pin "2") (pinfunction "GND_2") (pintype "power_in"))
      (node (ref "U6") (pin "A18") (pinfunction "GND_2_A18") (pintype "passive"))
      (node (ref "U6") (pin "A8") (pinfunction "GND_1_A8") (pintype "passive"))
      (node (ref "U6") (pin "B1") (pinfunction "GND_3_B1") (pintype "passive"))
      (node (ref "U6") (pin "B11") (pinfunction "GND_4_B11") (pintype "passive"))
      (node (ref "U6") (pin "C14") (pinfunction "GND_7_C14") (pintype "passive"))
      (node (ref "U6") (pin "C4") (pinfunction "GND_5_C4") (pintype "passive"))
      (node (ref "U6") (pin "C9") (pinfunction "GND_6_C9") (pintype "passive"))
      (node (ref "U6") (pin "D17") (pinfunction "GND_8_D17") (pintype "passive"))
      (node (ref "U6") (pin "E10") (pinfunction "GND_9_E10") (pintype "passive"))
      (node (ref "U6") (pin "E20") (pinfunction "GND_10_E20") (pintype "passive"))
      (node (ref "U6") (pin "F3") (pinfunction "GND_11_F3") (pintype "passive"))
      (node (ref "U6") (pin "F7") (pinfunction "GND_12_F7") (pintype "passive"))
      (node (ref "U6") (pin "G10") (pinfunction "GND_13_G10") (pintype "passive"))
      (node (ref "U6") (pin "G12") (pinfunction "GND_14_G12") (pintype "passive"))
      (node (ref "U6") (pin "G16") (pinfunction "GND_15_G16") (pintype "passive"))
      (node (ref "U6") (pin "H11") (pinfunction "GND_18_H11") (pintype "passive"))
      (node (ref "U6") (pin "H13") (pinfunction "GND_19_H13") (pintype "passive"))
      (node (ref "U6") (pin "H19") (pinfunction "GND_20_H19") (pintype "passive"))
      (node (ref "U6") (pin "H7") (pinfunction "GND_16_H7") (pintype "passive"))
      (node (ref "U6") (pin "H9") (pinfunction "GND_17_H9") (pintype "passive"))
      (node (ref "U6") (pin "J10") (pinfunction "GNDADC_0_J10") (pintype "passive"))
      (node (ref "U6") (pin "J12") (pinfunction "GND_23_J12") (pintype "passive"))
      (node (ref "U6") (pin "J2") (pinfunction "GND_21_J2") (pintype "passive"))
      (node (ref "U6") (pin "J8") (pinfunction "GND_22_J8") (pintype "passive"))
      (node (ref "U6") (pin "K10") (pinfunction "VREFN_0_K10") (pintype "passive"))
      (node (ref "U6") (pin "K11") (pinfunction "GND_26_K11") (pintype "passive"))
      (node (ref "U6") (pin "K13") (pinfunction "GND_27_K13") (pintype "passive"))
      (node (ref "U6") (pin "K15") (pinfunction "GND_28_K15") (pintype "passive"))
      (node (ref "U6") (pin "K5") (pinfunction "GND_24_K5") (pintype "passive"))
      (node (ref "U6") (pin "K7") (pinfunction "GND_25_K7") (pintype "passive"))
      (node (ref "U6") (pin "K9") (pinfunction "VP_0_K9") (pintype "passive"))
      (node (ref "U6") (pin "L10") (pinfunction "VN_0_L10") (pintype "passive"))
      (node (ref "U6") (pin "L12") (pinfunction "GND_30_L12") (pintype "passive"))
      (node (ref "U6") (pin "L18") (pinfunction "GND_31_L18") (pintype "passive"))
      (node (ref "U6") (pin "L8") (pinfunction "GND_29_L8") (pintype "passive"))
      (node (ref "U6") (pin "L9") (pinfunction "VREFP_0_L9") (pintype "passive"))
      (node (ref "U6") (pin "M1") (pinfunction "GND_32_M1") (pintype "passive"))
      (node (ref "U6") (pin "M11") (pinfunction "GND_34_M11") (pintype "passive"))
      (node (ref "U6") (pin "M13") (pinfunction "GND_35_M13") (pintype "passive"))
      (node (ref "U6") (pin "M7") (pinfunction "GND_33_M7") (pintype "passive"))
      (node (ref "U6") (pin "N10") (pinfunction "GND_38_N10") (pintype "passive"))
      (node (ref "U6") (pin "N12") (pinfunction "GND_39_N12") (pintype "passive"))
      (node (ref "U6") (pin "N14") (pinfunction "GND_40_N14") (pintype "passive"))
      (node (ref "U6") (pin "N4") (pinfunction "GND_36_N4") (pintype "passive"))
      (node (ref "U6") (pin "N8") (pinfunction "GND_37_N8") (pintype "passive"))
      (node (ref "U6") (pin "P11") (pinfunction "GND_43_P11") (pintype "passive"))
      (node (ref "U6") (pin "P13") (pinfunction "GND_44_P13") (pintype "passive"))
      (node (ref "U6") (pin "P17") (pinfunction "GND_45_P17") (pintype "passive"))
      (node (ref "U6") (pin "P7") (pinfunction "GND_41_P7") (pintype "passive"))
      (node (ref "U6") (pin "P9") (pinfunction "GND_42_P9") (pintype "passive"))
      (node (ref "U6") (pin "R12") (pinfunction "GND_47_R12") (pintype "passive"))
      (node (ref "U6") (pin "R20") (pinfunction "GND_48_R20") (pintype "passive"))
      (node (ref "U6") (pin "R8") (pinfunction "GND_46_R8") (pintype "passive"))
      (node (ref "U6") (pin "T13") (pinfunction "GND_51_T13") (pintype "passive"))
      (node (ref "U6") (pin "T3") (pinfunction "GND_49_T3") (pintype "passive"))
      (node (ref "U6") (pin "T7") (pinfunction "GND_50_T7") (pintype "passive"))
      (node (ref "U6") (pin "U16") (pinfunction "GND_53_U16") (pintype "passive"))
      (node (ref "U6") (pin "U6") (pinfunction "GND_52_U6") (pintype "passive"))
      (node (ref "U6") (pin "V19") (pinfunction "GND_55_V19") (pintype "passive"))
      (node (ref "U6") (pin "V9") (pinfunction "GND_54_V9") (pintype "passive"))
      (node (ref "U6") (pin "W12") (pinfunction "GND_57_W12") (pintype "passive"))
      (node (ref "U6") (pin "W2") (pinfunction "GND_56_W2") (pintype "passive"))
      (node (ref "U6") (pin "Y15") (pinfunction "GND_59_Y15") (pintype "passive"))
      (node (ref "U6") (pin "Y5") (pinfunction "GND_58_Y5") (pintype "passive"))
      (node (ref "U8") (pin "A9") (pinfunction "VSS_A9") (pintype "power_in"))
      (node (ref "U8") (pin "B1") (pinfunction "VSSQ_B1") (pintype "power_in"))
      (node (ref "U8") (pin "B3") (pinfunction "VSS_B3") (pintype "power_in"))
      (node (ref "U8") (pin "B9") (pinfunction "VSSQ_B9") (pintype "power_in"))
      (node (ref "U8") (pin "D1") (pinfunction "VSSQ_D1") (pintype "power_in"))
      (node (ref "U8") (pin "D8") (pinfunction "VSSQ_D8") (pintype "power_in"))
      (node (ref "U8") (pin "E1") (pinfunction "VSS_E1") (pintype "power_in"))
      (node (ref "U8") (pin "E2") (pinfunction "VSSQ_E2") (pintype "power_in"))
      (node (ref "U8") (pin "E8") (pinfunction "VSSQ_E8") (pintype "power_in"))
      (node (ref "U8") (pin "F9") (pinfunction "VSSQ_F9") (pintype "power_in"))
      (node (ref "U8") (pin "G1") (pinfunction "VSSQ_G1") (pintype "power_in"))
      (node (ref "U8") (pin "G8") (pinfunction "VSS_G8") (pintype "power_in"))
      (node (ref "U8") (pin "G9") (pinfunction "VSSQ_G9") (pintype "power_in"))
      (node (ref "U8") (pin "J2") (pinfunction "VSS_J2") (pintype "power_in"))
      (node (ref "U8") (pin "J8") (pinfunction "VSS_J8") (pintype "power_in"))
      (node (ref "U8") (pin "M1") (pinfunction "VSS_M1") (pintype "power_in"))
      (node (ref "U8") (pin "M9") (pinfunction "VSS_M9") (pintype "power_in"))
      (node (ref "U8") (pin "P1") (pinfunction "VSS_P1") (pintype "power_in"))
      (node (ref "U8") (pin "P9") (pinfunction "VSS_P9") (pintype "power_in"))
      (node (ref "U8") (pin "T1") (pinfunction "VSS_T1") (pintype "power_in"))
      (node (ref "U8") (pin "T9") (pinfunction "VSS_T9") (pintype "power_in"))
    )
    (net (code "62") (name "Net-(D-A)") (class "Default")
      (node (ref "D") (pin "2") (pinfunction "A_2") (pintype "passive"))
      (node (ref "R") (pin "2") (pinfunction "2_2") (pintype "passive"))
    )
    (net (code "63") (name "Net-(U6-PS_POR_B_500)") (class "Default")
      (node (ref "10K") (pin "1") (pinfunction "1_1") (pintype "passive"))
      (node (ref "Button") (pin "3") (pinfunction "3_3") (pintype "passive"))
      (node (ref "U6") (pin "C7") (pinfunction "PS_POR_B_500_C7") (pintype "passive"))
    )
    (net (code "64") (name "Net-(U7A-ZQ)") (class "Default")
      (node (ref "R3") (pin "1") (pinfunction "1_1") (pintype "passive"))
      (node (ref "U7") (pin "L8") (pinfunction "ZQ_L8") (pintype "passive"))
    )
    (net (code "65") (name "Net-(U8B-VREFCA)") (class "Default")
      (node (ref "R1") (pin "1") (pinfunction "1_1") (pintype "passive"))
      (node (ref "R2") (pin "2") (pinfunction "2_2") (pintype "passive"))
      (node (ref "U8") (pin "H1") (pinfunction "VREFDQ_H1") (pintype "power_in"))
      (node (ref "U8") (pin "M8") (pinfunction "VREFCA_M8") (pintype "power_in"))
    )
    (net (code "66") (name "unconnected-(Button-Pad1)") (class "Default")
      (node (ref "Button") (pin "1") (pinfunction "1_1") (pintype "passive"))
    )
    (net (code "67") (name "unconnected-(Button-Pad4)") (class "Default")
      (node (ref "Button") (pin "4") (pinfunction "4_4") (pintype "passive"))
    )
    (net (code "68") (name "unconnected-(J-D+-Pad3)") (class "Default")
      (node (ref "J") (pin "3") (pinfunction "D+_3") (pintype "passive"))
    )
    (net (code "69") (name "unconnected-(J-D--Pad2)") (class "Default")
      (node (ref "J") (pin "2") (pinfunction "D-_2") (pintype "passive"))
    )
    (net (code "70") (name "unconnected-(J-ID-Pad4)") (class "Default")
      (node (ref "J") (pin "4") (pinfunction "ID_4") (pintype "passive"))
    )
    (net (code "71") (name "unconnected-(U4-Ground-Pad1)") (class "Default")
      (node (ref "U4") (pin "1") (pinfunction "Ground_1") (pintype "power_in"))
    )
    (net (code "72") (name "unconnected-(U6-DONE_0-PadR11)") (class "Default")
      (node (ref "U6") (pin "R11") (pinfunction "DONE_0_R11") (pintype "passive"))
    )
    (net (code "73") (name "unconnected-(U6-DXN_0-PadM10)") (class "Default")
      (node (ref "U6") (pin "M10") (pinfunction "DXN_0_M10") (pintype "passive"))
    )
    (net (code "74") (name "unconnected-(U6-DXP_0-PadM9)") (class "Default")
      (node (ref "U6") (pin "M9") (pinfunction "DXP_0_M9") (pintype "passive"))
    )
    (net (code "75") (name "unconnected-(U6-INIT_B_0-PadR10)") (class "Default")
      (node (ref "U6") (pin "R10") (pinfunction "INIT_B_0_R10") (pintype "passive"))
    )
    (net (code "76") (name "unconnected-(U6-IO_0_34-PadR19)") (class "Default")
      (node (ref "U6") (pin "R19") (pinfunction "IO_0_34_R19") (pintype "passive"))
    )
    (net (code "77") (name "unconnected-(U6-IO_0_35-PadG14)") (class "Default")
      (node (ref "U6") (pin "G14") (pinfunction "IO_0_35_G14") (pintype "passive"))
    )
    (net (code "78") (name "unconnected-(U6-IO_25_34-PadT19)") (class "Default")
      (node (ref "U6") (pin "T19") (pinfunction "IO_25_34_T19") (pintype "passive"))
    )
    (net (code "79") (name "unconnected-(U6-IO_25_35-PadJ15)") (class "Default")
      (node (ref "U6") (pin "J15") (pinfunction "IO_25_35_J15") (pintype "passive"))
    )
    (net (code "80") (name "unconnected-(U6-IO_L1N_T0_34-PadT10)") (class "Default")
      (node (ref "U6") (pin "T10") (pinfunction "IO_L1N_T0_34_T10") (pintype "passive"))
    )
    (net (code "81") (name "unconnected-(U6-IO_L1N_T0_AD0N_35-PadB20)") (class "Default")
      (node (ref "U6") (pin "B20") (pinfunction "IO_L1N_T0_AD0N_35_B20") (pintype "passive"))
    )
    (net (code "82") (name "unconnected-(U6-IO_L1P_T0_34-PadT11)") (class "Default")
      (node (ref "U6") (pin "T11") (pinfunction "IO_L1P_T0_34_T11") (pintype "passive"))
    )
    (net (code "83") (name "unconnected-(U6-IO_L1P_T0_AD0P_35-PadC20)") (class "Default")
      (node (ref "U6") (pin "C20") (pinfunction "IO_L1P_T0_AD0P_35_C20") (pintype "passive"))
    )
    (net (code "84") (name "unconnected-(U6-IO_L2N_T0_34-PadU12)") (class "Default")
      (node (ref "U6") (pin "U12") (pinfunction "IO_L2N_T0_34_U12") (pintype "passive"))
    )
    (net (code "85") (name "unconnected-(U6-IO_L2N_T0_AD8N_35-PadA20)") (class "Default")
      (node (ref "U6") (pin "A20") (pinfunction "IO_L2N_T0_AD8N_35_A20") (pintype "passive"))
    )
    (net (code "86") (name "unconnected-(U6-IO_L2P_T0_34-PadT12)") (class "Default")
      (node (ref "U6") (pin "T12") (pinfunction "IO_L2P_T0_34_T12") (pintype "passive"))
    )
    (net (code "87") (name "unconnected-(U6-IO_L2P_T0_AD8P_35-PadB19)") (class "Default")
      (node (ref "U6") (pin "B19") (pinfunction "IO_L2P_T0_AD8P_35_B19") (pintype "passive"))
    )
    (net (code "88") (name "unconnected-(U6-IO_L3N_T0_DQS_34-PadV13)") (class "Default")
      (node (ref "U6") (pin "V13") (pinfunction "IO_L3N_T0_DQS_34_V13") (pintype "passive"))
    )
    (net (code "89") (name "unconnected-(U6-IO_L3N_T0_DQS_AD1N_35-PadD18)") (class "Default")
      (node (ref "U6") (pin "D18") (pinfunction "IO_L3N_T0_DQS_AD1N_35_D18") (pintype "passive"))
    )
    (net (code "90") (name "unconnected-(U6-IO_L3P_T0_DQS_AD1P_35-PadE17)") (class "Default")
      (node (ref "U6") (pin "E17") (pinfunction "IO_L3P_T0_DQS_AD1P_35_E17") (pintype "passive"))
    )
    (net (code "91") (name "unconnected-(U6-IO_L3P_T0_DQS_PUDC_B_34-PadU13)") (class "Default")
      (node (ref "U6") (pin "U13") (pinfunction "IO_L3P_T0_DQS_PUDC_B_34_U13") (pintype "passive"))
    )
    (net (code "92") (name "unconnected-(U6-IO_L4N_T0_34-PadW13)") (class "Default")
      (node (ref "U6") (pin "W13") (pinfunction "IO_L4N_T0_34_W13") (pintype "passive"))
    )
    (net (code "93") (name "unconnected-(U6-IO_L4N_T0_35-PadD20)") (class "Default")
      (node (ref "U6") (pin "D20") (pinfunction "IO_L4N_T0_35_D20") (pintype "passive"))
    )
    (net (code "94") (name "unconnected-(U6-IO_L4P_T0_34-PadV12)") (class "Default")
      (node (ref "U6") (pin "V12") (pinfunction "IO_L4P_T0_34_V12") (pintype "passive"))
    )
    (net (code "95") (name "unconnected-(U6-IO_L4P_T0_35-PadD19)") (class "Default")
      (node (ref "U6") (pin "D19") (pinfunction "IO_L4P_T0_35_D19") (pintype "passive"))
    )
    (net (code "96") (name "unconnected-(U6-IO_L5N_T0_34-PadT15)") (class "Default")
      (node (ref "U6") (pin "T15") (pinfunction "IO_L5N_T0_34_T15") (pintype "passive"))
    )
    (net (code "97") (name "unconnected-(U6-IO_L5N_T0_AD9N_35-PadE19)") (class "Default")
      (node (ref "U6") (pin "E19") (pinfunction "IO_L5N_T0_AD9N_35_E19") (pintype "passive"))
    )
    (net (code "98") (name "unconnected-(U6-IO_L5P_T0_34-PadT14)") (class "Default")
      (node (ref "U6") (pin "T14") (pinfunction "IO_L5P_T0_34_T14") (pintype "passive"))
    )
    (net (code "99") (name "unconnected-(U6-IO_L5P_T0_AD9P_35-PadE18)") (class "Default")
      (node (ref "U6") (pin "E18") (pinfunction "IO_L5P_T0_AD9P_35_E18") (pintype "passive"))
    )
    (net (code "100") (name "unconnected-(U6-IO_L6N_T0_VREF_34-PadR14)") (class "Default")
      (node (ref "U6") (pin "R14") (pinfunction "IO_L6N_T0_VREF_34_R14") (pintype "passive"))
    )
    (net (code "101") (name "unconnected-(U6-IO_L6N_T0_VREF_35-PadF17)") (class "Default")
      (node (ref "U6") (pin "F17") (pinfunction "IO_L6N_T0_VREF_35_F17") (pintype "passive"))
    )
    (net (code "102") (name "unconnected-(U6-IO_L6P_T0_34-PadP14)") (class "Default")
      (node (ref "U6") (pin "P14") (pinfunction "IO_L6P_T0_34_P14") (pintype "passive"))
    )
    (net (code "103") (name "unconnected-(U6-IO_L6P_T0_35-PadF16)") (class "Default")
      (node (ref "U6") (pin "F16") (pinfunction "IO_L6P_T0_35_F16") (pintype "passive"))
    )
    (net (code "104") (name "unconnected-(U6-IO_L7N_T1_34-PadY17)") (class "Default")
      (node (ref "U6") (pin "Y17") (pinfunction "IO_L7N_T1_34_Y17") (pintype "passive"))
    )
    (net (code "105") (name "unconnected-(U6-IO_L7N_T1_AD2N_35-PadM20)") (class "Default")
      (node (ref "U6") (pin "M20") (pinfunction "IO_L7N_T1_AD2N_35_M20") (pintype "passive"))
    )
    (net (code "106") (name "unconnected-(U6-IO_L7P_T1_34-PadY16)") (class "Default")
      (node (ref "U6") (pin "Y16") (pinfunction "IO_L7P_T1_34_Y16") (pintype "passive"))
    )
    (net (code "107") (name "unconnected-(U6-IO_L8N_T1_34-PadY14)") (class "Default")
      (node (ref "U6") (pin "Y14") (pinfunction "IO_L8N_T1_34_Y14") (pintype "passive"))
    )
    (net (code "108") (name "unconnected-(U6-IO_L8N_T1_AD10N_35-PadM18)") (class "Default")
      (node (ref "U6") (pin "M18") (pinfunction "IO_L8N_T1_AD10N_35_M18") (pintype "passive"))
    )
    (net (code "109") (name "unconnected-(U6-IO_L8P_T1_34-PadW14)") (class "Default")
      (node (ref "U6") (pin "W14") (pinfunction "IO_L8P_T1_34_W14") (pintype "passive"))
    )
    (net (code "110") (name "unconnected-(U6-IO_L8P_T1_AD10P_35-PadM17)") (class "Default")
      (node (ref "U6") (pin "M17") (pinfunction "IO_L8P_T1_AD10P_35_M17") (pintype "passive"))
    )
    (net (code "111") (name "unconnected-(U6-IO_L9N_T1_DQS_34-PadU17)") (class "Default")
      (node (ref "U6") (pin "U17") (pinfunction "IO_L9N_T1_DQS_34_U17") (pintype "passive"))
    )
    (net (code "112") (name "unconnected-(U6-IO_L9N_T1_DQS_AD3N_35-PadL20)") (class "Default")
      (node (ref "U6") (pin "L20") (pinfunction "IO_L9N_T1_DQS_AD3N_35_L20") (pintype "passive"))
    )
    (net (code "113") (name "unconnected-(U6-IO_L9P_T1_DQS_34-PadT16)") (class "Default")
      (node (ref "U6") (pin "T16") (pinfunction "IO_L9P_T1_DQS_34_T16") (pintype "passive"))
    )
    (net (code "114") (name "unconnected-(U6-IO_L9P_T1_DQS_AD3P_35-PadL19)") (class "Default")
      (node (ref "U6") (pin "L19") (pinfunction "IO_L9P_T1_DQS_AD3P_35_L19") (pintype "passive"))
    )
    (net (code "115") (name "unconnected-(U6-IO_L10N_T1_34-PadW15)") (class "Default")
      (node (ref "U6") (pin "W15") (pinfunction "IO_L10N_T1_34_W15") (pintype "passive"))
    )
    (net (code "116") (name "unconnected-(U6-IO_L10N_T1_AD11N_35-PadJ19)") (class "Default")
      (node (ref "U6") (pin "J19") (pinfunction "IO_L10N_T1_AD11N_35_J19") (pintype "passive"))
    )
    (net (code "117") (name "unconnected-(U6-IO_L10P_T1_34-PadV15)") (class "Default")
      (node (ref "U6") (pin "V15") (pinfunction "IO_L10P_T1_34_V15") (pintype "passive"))
    )
    (net (code "118") (name "unconnected-(U6-IO_L10P_T1_AD11P_35-PadK19)") (class "Default")
      (node (ref "U6") (pin "K19") (pinfunction "IO_L10P_T1_AD11P_35_K19") (pintype "passive"))
    )
    (net (code "119") (name "unconnected-(U6-IO_L11N_T1_SRCC_34-PadU15)") (class "Default")
      (node (ref "U6") (pin "U15") (pinfunction "IO_L11N_T1_SRCC_34_U15") (pintype "passive"))
    )
    (net (code "120") (name "unconnected-(U6-IO_L11N_T1_SRCC_35-PadL17)") (class "Default")
      (node (ref "U6") (pin "L17") (pinfunction "IO_L11N_T1_SRCC_35_L17") (pintype "passive"))
    )
    (net (code "121") (name "unconnected-(U6-IO_L11P_T1_SRCC_34-PadU14)") (class "Default")
      (node (ref "U6") (pin "U14") (pinfunction "IO_L11P_T1_SRCC_34_U14") (pintype "passive"))
    )
    (net (code "122") (name "unconnected-(U6-IO_L11P_T1_SRCC_35-PadL16)") (class "Default")
      (node (ref "U6") (pin "L16") (pinfunction "IO_L11P_T1_SRCC_35_L16") (pintype "passive"))
    )
    (net (code "123") (name "unconnected-(U6-IO_L12N_T1_MRCC_34-PadU19)") (class "Default")
      (node (ref "U6") (pin "U19") (pinfunction "IO_L12N_T1_MRCC_34_U19") (pintype "passive"))
    )
    (net (code "124") (name "unconnected-(U6-IO_L12N_T1_MRCC_35-PadK18)") (class "Default")
      (node (ref "U6") (pin "K18") (pinfunction "IO_L12N_T1_MRCC_35_K18") (pintype "passive"))
    )
    (net (code "125") (name "unconnected-(U6-IO_L12P_T1_MRCC_34-PadU18)") (class "Default")
      (node (ref "U6") (pin "U18") (pinfunction "IO_L12P_T1_MRCC_34_U18") (pintype "passive"))
    )
    (net (code "126") (name "unconnected-(U6-IO_L12P_T1_MRCC_35-PadK17)") (class "Default")
      (node (ref "U6") (pin "K17") (pinfunction "IO_L12P_T1_MRCC_35_K17") (pintype "passive"))
    )
    (net (code "127") (name "unconnected-(U6-IO_L13N_T2_MRCC_34-PadP19)") (class "Default")
      (node (ref "U6") (pin "P19") (pinfunction "IO_L13N_T2_MRCC_34_P19") (pintype "passive"))
    )
    (net (code "128") (name "unconnected-(U6-IO_L13N_T2_MRCC_35-PadH17)") (class "Default")
      (node (ref "U6") (pin "H17") (pinfunction "IO_L13N_T2_MRCC_35_H17") (pintype "passive"))
    )
    (net (code "129") (name "unconnected-(U6-IO_L13P_T2_MRCC_34-PadN18)") (class "Default")
      (node (ref "U6") (pin "N18") (pinfunction "IO_L13P_T2_MRCC_34_N18") (pintype "passive"))
    )
    (net (code "130") (name "unconnected-(U6-IO_L13P_T2_MRCC_35-PadH16)") (class "Default")
      (node (ref "U6") (pin "H16") (pinfunction "IO_L13P_T2_MRCC_35_H16") (pintype "passive"))
    )
    (net (code "131") (name "unconnected-(U6-IO_L14N_T2_AD4N_SRCC_35-PadH18)") (class "Default")
      (node (ref "U6") (pin "H18") (pinfunction "IO_L14N_T2_AD4N_SRCC_35_H18") (pintype "passive"))
    )
    (net (code "132") (name "unconnected-(U6-IO_L14N_T2_SRCC_34-PadP20)") (class "Default")
      (node (ref "U6") (pin "P20") (pinfunction "IO_L14N_T2_SRCC_34_P20") (pintype "passive"))
    )
    (net (code "133") (name "unconnected-(U6-IO_L14P_T2_AD4P_SRCC_35-PadJ18)") (class "Default")
      (node (ref "U6") (pin "J18") (pinfunction "IO_L14P_T2_AD4P_SRCC_35_J18") (pintype "passive"))
    )
    (net (code "134") (name "unconnected-(U6-IO_L14P_T2_SRCC_34-PadN20)") (class "Default")
      (node (ref "U6") (pin "N20") (pinfunction "IO_L14P_T2_SRCC_34_N20") (pintype "passive"))
    )
    (net (code "135") (name "unconnected-(U6-IO_L15N_T2_DQS_34-PadU20)") (class "Default")
      (node (ref "U6") (pin "U20") (pinfunction "IO_L15N_T2_DQS_34_U20") (pintype "passive"))
    )
    (net (code "136") (name "unconnected-(U6-IO_L15N_T2_DQS_AD12N_35-PadF20)") (class "Default")
      (node (ref "U6") (pin "F20") (pinfunction "IO_L15N_T2_DQS_AD12N_35_F20") (pintype "passive"))
    )
    (net (code "137") (name "unconnected-(U6-IO_L15P_T2_DQS_34-PadT20)") (class "Default")
      (node (ref "U6") (pin "T20") (pinfunction "IO_L15P_T2_DQS_34_T20") (pintype "passive"))
    )
    (net (code "138") (name "unconnected-(U6-IO_L15P_T2_DQS_AD12P_35-PadF19)") (class "Default")
      (node (ref "U6") (pin "F19") (pinfunction "IO_L15P_T2_DQS_AD12P_35_F19") (pintype "passive"))
    )
    (net (code "139") (name "unconnected-(U6-IO_L16N_T2_34-PadW20)") (class "Default")
      (node (ref "U6") (pin "W20") (pinfunction "IO_L16N_T2_34_W20") (pintype "passive"))
    )
    (net (code "140") (name "unconnected-(U6-IO_L16N_T2_35-PadG18)") (class "Default")
      (node (ref "U6") (pin "G18") (pinfunction "IO_L16N_T2_35_G18") (pintype "passive"))
    )
    (net (code "141") (name "unconnected-(U6-IO_L16P_T2_34-PadV20)") (class "Default")
      (node (ref "U6") (pin "V20") (pinfunction "IO_L16P_T2_34_V20") (pintype "passive"))
    )
    (net (code "142") (name "unconnected-(U6-IO_L16P_T2_35-PadG17)") (class "Default")
      (node (ref "U6") (pin "G17") (pinfunction "IO_L16P_T2_35_G17") (pintype "passive"))
    )
    (net (code "143") (name "unconnected-(U6-IO_L17N_T2_34-PadY19)") (class "Default")
      (node (ref "U6") (pin "Y19") (pinfunction "IO_L17N_T2_34_Y19") (pintype "passive"))
    )
    (net (code "144") (name "unconnected-(U6-IO_L17N_T2_AD5N_35-PadH20)") (class "Default")
      (node (ref "U6") (pin "H20") (pinfunction "IO_L17N_T2_AD5N_35_H20") (pintype "passive"))
    )
    (net (code "145") (name "unconnected-(U6-IO_L17P_T2_34-PadY18)") (class "Default")
      (node (ref "U6") (pin "Y18") (pinfunction "IO_L17P_T2_34_Y18") (pintype "passive"))
    )
    (net (code "146") (name "unconnected-(U6-IO_L17P_T2_AD5P_35-PadJ20)") (class "Default")
      (node (ref "U6") (pin "J20") (pinfunction "IO_L17P_T2_AD5P_35_J20") (pintype "passive"))
    )
    (net (code "147") (name "unconnected-(U6-IO_L18N_T2_34-PadW16)") (class "Default")
      (node (ref "U6") (pin "W16") (pinfunction "IO_L18N_T2_34_W16") (pintype "passive"))
    )
    (net (code "148") (name "unconnected-(U6-IO_L18N_T2_AD13N_35-PadG20)") (class "Default")
      (node (ref "U6") (pin "G20") (pinfunction "IO_L18N_T2_AD13N_35_G20") (pintype "passive"))
    )
    (net (code "149") (name "unconnected-(U6-IO_L18P_T2_34-PadV16)") (class "Default")
      (node (ref "U6") (pin "V16") (pinfunction "IO_L18P_T2_34_V16") (pintype "passive"))
    )
    (net (code "150") (name "unconnected-(U6-IO_L18P_T2_AD13P_35-PadG19)") (class "Default")
      (node (ref "U6") (pin "G19") (pinfunction "IO_L18P_T2_AD13P_35_G19") (pintype "passive"))
    )
    (net (code "151") (name "unconnected-(U6-IO_L19N_T3_VREF_34-PadR17)") (class "Default")
      (node (ref "U6") (pin "R17") (pinfunction "IO_L19N_T3_VREF_34_R17") (pintype "passive"))
    )
    (net (code "152") (name "unconnected-(U6-IO_L19N_T3_VREF_35-PadG15)") (class "Default")
      (node (ref "U6") (pin "G15") (pinfunction "IO_L19N_T3_VREF_35_G15") (pintype "passive"))
    )
    (net (code "153") (name "unconnected-(U6-IO_L19P_T3_34-PadR16)") (class "Default")
      (node (ref "U6") (pin "R16") (pinfunction "IO_L19P_T3_34_R16") (pintype "passive"))
    )
    (net (code "154") (name "unconnected-(U6-IO_L19P_T3_35-PadH15)") (class "Default")
      (node (ref "U6") (pin "H15") (pinfunction "IO_L19P_T3_35_H15") (pintype "passive"))
    )
    (net (code "155") (name "unconnected-(U6-IO_L20N_T3_34-PadR18)") (class "Default")
      (node (ref "U6") (pin "R18") (pinfunction "IO_L20N_T3_34_R18") (pintype "passive"))
    )
    (net (code "156") (name "unconnected-(U6-IO_L20N_T3_AD6N_35-PadJ14)") (class "Default")
      (node (ref "U6") (pin "J14") (pinfunction "IO_L20N_T3_AD6N_35_J14") (pintype "passive"))
    )
    (net (code "157") (name "unconnected-(U6-IO_L20P_T3_34-PadT17)") (class "Default")
      (node (ref "U6") (pin "T17") (pinfunction "IO_L20P_T3_34_T17") (pintype "passive"))
    )
    (net (code "158") (name "unconnected-(U6-IO_L20P_T3_AD6P_35-PadK14)") (class "Default")
      (node (ref "U6") (pin "K14") (pinfunction "IO_L20P_T3_AD6P_35_K14") (pintype "passive"))
    )
    (net (code "159") (name "unconnected-(U6-IO_L21N_T3_DQS_34-PadV18)") (class "Default")
      (node (ref "U6") (pin "V18") (pinfunction "IO_L21N_T3_DQS_34_V18") (pintype "passive"))
    )
    (net (code "160") (name "unconnected-(U6-IO_L21N_T3_DQS_AD14N_35-PadN16)") (class "Default")
      (node (ref "U6") (pin "N16") (pinfunction "IO_L21N_T3_DQS_AD14N_35_N16") (pintype "passive"))
    )
    (net (code "161") (name "unconnected-(U6-IO_L21P_T3_DQS_34-PadV17)") (class "Default")
      (node (ref "U6") (pin "V17") (pinfunction "IO_L21P_T3_DQS_34_V17") (pintype "passive"))
    )
    (net (code "162") (name "unconnected-(U6-IO_L21P_T3_DQS_AD14P_35-PadN15)") (class "Default")
      (node (ref "U6") (pin "N15") (pinfunction "IO_L21P_T3_DQS_AD14P_35_N15") (pintype "passive"))
    )
    (net (code "163") (name "unconnected-(U6-IO_L22N_T3_34-PadW19)") (class "Default")
      (node (ref "U6") (pin "W19") (pinfunction "IO_L22N_T3_34_W19") (pintype "passive"))
    )
    (net (code "164") (name "unconnected-(U6-IO_L22N_T3_AD7N_35-PadL15)") (class "Default")
      (node (ref "U6") (pin "L15") (pinfunction "IO_L22N_T3_AD7N_35_L15") (pintype "passive"))
    )
    (net (code "165") (name "unconnected-(U6-IO_L22P_T3_34-PadW18)") (class "Default")
      (node (ref "U6") (pin "W18") (pinfunction "IO_L22P_T3_34_W18") (pintype "passive"))
    )
    (net (code "166") (name "unconnected-(U6-IO_L22P_T3_AD7P_35-PadL14)") (class "Default")
      (node (ref "U6") (pin "L14") (pinfunction "IO_L22P_T3_AD7P_35_L14") (pintype "passive"))
    )
    (net (code "167") (name "unconnected-(U6-IO_L23N_T3_34-PadP18)") (class "Default")
      (node (ref "U6") (pin "P18") (pinfunction "IO_L23N_T3_34_P18") (pintype "passive"))
    )
    (net (code "168") (name "unconnected-(U6-IO_L23N_T3_35-PadM15)") (class "Default")
      (node (ref "U6") (pin "M15") (pinfunction "IO_L23N_T3_35_M15") (pintype "passive"))
    )
    (net (code "169") (name "unconnected-(U6-IO_L23P_T3_34-PadN17)") (class "Default")
      (node (ref "U6") (pin "N17") (pinfunction "IO_L23P_T3_34_N17") (pintype "passive"))
    )
    (net (code "170") (name "unconnected-(U6-IO_L23P_T3_35-PadM14)") (class "Default")
      (node (ref "U6") (pin "M14") (pinfunction "IO_L23P_T3_35_M14") (pintype "passive"))
    )
    (net (code "171") (name "unconnected-(U6-IO_L24N_T3_34-PadP16)") (class "Default")
      (node (ref "U6") (pin "P16") (pinfunction "IO_L24N_T3_34_P16") (pintype "passive"))
    )
    (net (code "172") (name "unconnected-(U6-IO_L24N_T3_AD15N_35-PadJ16)") (class "Default")
      (node (ref "U6") (pin "J16") (pinfunction "IO_L24N_T3_AD15N_35_J16") (pintype "passive"))
    )
    (net (code "173") (name "unconnected-(U6-IO_L24P_T3_34-PadP15)") (class "Default")
      (node (ref "U6") (pin "P15") (pinfunction "IO_L24P_T3_34_P15") (pintype "passive"))
    )
    (net (code "174") (name "unconnected-(U6-IO_L24P_T3_AD15P_35-PadK16)") (class "Default")
      (node (ref "U6") (pin "K16") (pinfunction "IO_L24P_T3_AD15P_35_K16") (pintype "passive"))
    )
    (net (code "175") (name "unconnected-(U6-NC_1-PadT5)") (class "Default")
      (node (ref "U6") (pin "T5") (pinfunction "NC_1_T5") (pintype "passive"))
    )
    (net (code "176") (name "unconnected-(U6-NC_2-PadT9)") (class "Default")
      (node (ref "U6") (pin "T9") (pinfunction "NC_2_T9") (pintype "passive"))
    )
    (net (code "177") (name "unconnected-(U6-NC_3-PadU5)") (class "Default")
      (node (ref "U6") (pin "U5") (pinfunction "NC_3_U5") (pintype "passive"))
    )
    (net (code "178") (name "unconnected-(U6-NC_4-PadU7)") (class "Default")
      (node (ref "U6") (pin "U7") (pinfunction "NC_4_U7") (pintype "passive"))
    )
    (net (code "179") (name "unconnected-(U6-NC_5-PadU8)") (class "Default")
      (node (ref "U6") (pin "U8") (pinfunction "NC_5_U8") (pintype "passive"))
    )
    (net (code "180") (name "unconnected-(U6-NC_6-PadU9)") (class "Default")
      (node (ref "U6") (pin "U9") (pinfunction "NC_6_U9") (pintype "passive"))
    )
    (net (code "181") (name "unconnected-(U6-NC_7-PadU10)") (class "Default")
      (node (ref "U6") (pin "U10") (pinfunction "NC_7_U10") (pintype "passive"))
    )
    (net (code "182") (name "unconnected-(U6-NC_8-PadV5)") (class "Default")
      (node (ref "U6") (pin "V5") (pinfunction "NC_8_V5") (pintype "passive"))
    )
    (net (code "183") (name "unconnected-(U6-NC_9-PadV6)") (class "Default")
      (node (ref "U6") (pin "V6") (pinfunction "NC_9_V6") (pintype "passive"))
    )
    (net (code "184") (name "unconnected-(U6-NC_10-PadV7)") (class "Default")
      (node (ref "U6") (pin "V7") (pinfunction "NC_10_V7") (pintype "passive"))
    )
    (net (code "185") (name "unconnected-(U6-NC_11-PadV8)") (class "Default")
      (node (ref "U6") (pin "V8") (pinfunction "NC_11_V8") (pintype "passive"))
    )
    (net (code "186") (name "unconnected-(U6-NC_12-PadV10)") (class "Default")
      (node (ref "U6") (pin "V10") (pinfunction "NC_12_V10") (pintype "passive"))
    )
    (net (code "187") (name "unconnected-(U6-NC_13-PadV11)") (class "Default")
      (node (ref "U6") (pin "V11") (pinfunction "NC_13_V11") (pintype "passive"))
    )
    (net (code "188") (name "unconnected-(U6-NC_14-PadW6)") (class "Default")
      (node (ref "U6") (pin "W6") (pinfunction "NC_14_W6") (pintype "passive"))
    )
    (net (code "189") (name "unconnected-(U6-NC_15-PadW8)") (class "Default")
      (node (ref "U6") (pin "W8") (pinfunction "NC_15_W8") (pintype "passive"))
    )
    (net (code "190") (name "unconnected-(U6-NC_16-PadW9)") (class "Default")
      (node (ref "U6") (pin "W9") (pinfunction "NC_16_W9") (pintype "passive"))
    )
    (net (code "191") (name "unconnected-(U6-NC_17-PadW10)") (class "Default")
      (node (ref "U6") (pin "W10") (pinfunction "NC_17_W10") (pintype "passive"))
    )
    (net (code "192") (name "unconnected-(U6-NC_18-PadW11)") (class "Default")
      (node (ref "U6") (pin "W11") (pinfunction "NC_18_W11") (pintype "passive"))
    )
    (net (code "193") (name "unconnected-(U6-NC_19-PadY6)") (class "Default")
      (node (ref "U6") (pin "Y6") (pinfunction "NC_19_Y6") (pintype "passive"))
    )
    (net (code "194") (name "unconnected-(U6-NC_20-PadY7)") (class "Default")
      (node (ref "U6") (pin "Y7") (pinfunction "NC_20_Y7") (pintype "passive"))
    )
    (net (code "195") (name "unconnected-(U6-NC_21-PadY8)") (class "Default")
      (node (ref "U6") (pin "Y8") (pinfunction "NC_21_Y8") (pintype "passive"))
    )
    (net (code "196") (name "unconnected-(U6-NC_22-PadY9)") (class "Default")
      (node (ref "U6") (pin "Y9") (pinfunction "NC_22_Y9") (pintype "passive"))
    )
    (net (code "197") (name "unconnected-(U6-NC_23-PadY11)") (class "Default")
      (node (ref "U6") (pin "Y11") (pinfunction "NC_23_Y11") (pintype "passive"))
    )
    (net (code "198") (name "unconnected-(U6-NC_24-PadY12)") (class "Default")
      (node (ref "U6") (pin "Y12") (pinfunction "NC_24_Y12") (pintype "passive"))
    )
    (net (code "199") (name "unconnected-(U6-NC_25-PadY13)") (class "Default")
      (node (ref "U6") (pin "Y13") (pinfunction "NC_25_Y13") (pintype "passive"))
    )
    (net (code "200") (name "unconnected-(U6-PROGRAM_B_0-PadL6)") (class "Default")
      (node (ref "U6") (pin "L6") (pinfunction "PROGRAM_B_0_L6") (pintype "passive"))
    )
    (net (code "201") (name "unconnected-(U6-PS_DDR_DM2_502-PadT1)") (class "Default")
      (node (ref "U6") (pin "T1") (pinfunction "PS_DDR_DM2_502_T1") (pintype "passive"))
    )
    (net (code "202") (name "unconnected-(U6-PS_DDR_DM3_502-PadY1)") (class "Default")
      (node (ref "U6") (pin "Y1") (pinfunction "PS_DDR_DM3_502_Y1") (pintype "passive"))
    )
    (net (code "203") (name "unconnected-(U6-PS_DDR_DQ16_502-PadP1)") (class "Default")
      (node (ref "U6") (pin "P1") (pinfunction "PS_DDR_DQ16_502_P1") (pintype "passive"))
    )
    (net (code "204") (name "unconnected-(U6-PS_DDR_DQ17_502-PadP3)") (class "Default")
      (node (ref "U6") (pin "P3") (pinfunction "PS_DDR_DQ17_502_P3") (pintype "passive"))
    )
    (net (code "205") (name "unconnected-(U6-PS_DDR_DQ18_502-PadR3)") (class "Default")
      (node (ref "U6") (pin "R3") (pinfunction "PS_DDR_DQ18_502_R3") (pintype "passive"))
    )
    (net (code "206") (name "unconnected-(U6-PS_DDR_DQ19_502-PadR1)") (class "Default")
      (node (ref "U6") (pin "R1") (pinfunction "PS_DDR_DQ19_502_R1") (pintype "passive"))
    )
    (net (code "207") (name "unconnected-(U6-PS_DDR_DQ20_502-PadT4)") (class "Default")
      (node (ref "U6") (pin "T4") (pinfunction "PS_DDR_DQ20_502_T4") (pintype "passive"))
    )
    (net (code "208") (name "unconnected-(U6-PS_DDR_DQ21_502-PadU4)") (class "Default")
      (node (ref "U6") (pin "U4") (pinfunction "PS_DDR_DQ21_502_U4") (pintype "passive"))
    )
    (net (code "209") (name "unconnected-(U6-PS_DDR_DQ22_502-PadU2)") (class "Default")
      (node (ref "U6") (pin "U2") (pinfunction "PS_DDR_DQ22_502_U2") (pintype "passive"))
    )
    (net (code "210") (name "unconnected-(U6-PS_DDR_DQ23_502-PadU3)") (class "Default")
      (node (ref "U6") (pin "U3") (pinfunction "PS_DDR_DQ23_502_U3") (pintype "passive"))
    )
    (net (code "211") (name "unconnected-(U6-PS_DDR_DQ24_502-PadV1)") (class "Default")
      (node (ref "U6") (pin "V1") (pinfunction "PS_DDR_DQ24_502_V1") (pintype "passive"))
    )
    (net (code "212") (name "unconnected-(U6-PS_DDR_DQ25_502-PadY3)") (class "Default")
      (node (ref "U6") (pin "Y3") (pinfunction "PS_DDR_DQ25_502_Y3") (pintype "passive"))
    )
    (net (code "213") (name "unconnected-(U6-PS_DDR_DQ26_502-PadW1)") (class "Default")
      (node (ref "U6") (pin "W1") (pinfunction "PS_DDR_DQ26_502_W1") (pintype "passive"))
    )
    (net (code "214") (name "unconnected-(U6-PS_DDR_DQ27_502-PadY4)") (class "Default")
      (node (ref "U6") (pin "Y4") (pinfunction "PS_DDR_DQ27_502_Y4") (pintype "passive"))
    )
    (net (code "215") (name "unconnected-(U6-PS_DDR_DQ28_502-PadY2)") (class "Default")
      (node (ref "U6") (pin "Y2") (pinfunction "PS_DDR_DQ28_502_Y2") (pintype "passive"))
    )
    (net (code "216") (name "unconnected-(U6-PS_DDR_DQ29_502-PadW3)") (class "Default")
      (node (ref "U6") (pin "W3") (pinfunction "PS_DDR_DQ29_502_W3") (pintype "passive"))
    )
    (net (code "217") (name "unconnected-(U6-PS_DDR_DQ30_502-PadV2)") (class "Default")
      (node (ref "U6") (pin "V2") (pinfunction "PS_DDR_DQ30_502_V2") (pintype "passive"))
    )
    (net (code "218") (name "unconnected-(U6-PS_DDR_DQ31_502-PadV3)") (class "Default")
      (node (ref "U6") (pin "V3") (pinfunction "PS_DDR_DQ31_502_V3") (pintype "passive"))
    )
    (net (code "219") (name "unconnected-(U6-PS_DDR_DQS_N2_502-PadT2)") (class "Default")
      (node (ref "U6") (pin "T2") (pinfunction "PS_DDR_DQS_N2_502_T2") (pintype "passive"))
    )
    (net (code "220") (name "unconnected-(U6-PS_DDR_DQS_N3_502-PadW4)") (class "Default")
      (node (ref "U6") (pin "W4") (pinfunction "PS_DDR_DQS_N3_502_W4") (pintype "passive"))
    )
    (net (code "221") (name "unconnected-(U6-PS_DDR_DQS_P2_502-PadR2)") (class "Default")
      (node (ref "U6") (pin "R2") (pinfunction "PS_DDR_DQS_P2_502_R2") (pintype "passive"))
    )
    (net (code "222") (name "unconnected-(U6-PS_DDR_DQS_P3_502-PadW5)") (class "Default")
      (node (ref "U6") (pin "W5") (pinfunction "PS_DDR_DQS_P3_502_W5") (pintype "passive"))
    )
    (net (code "223") (name "unconnected-(U6-PS_DDR_VREF0_502-PadH6)") (class "Default")
      (node (ref "U6") (pin "H6") (pinfunction "PS_DDR_VREF0_502_H6") (pintype "passive"))
    )
    (net (code "224") (name "unconnected-(U6-PS_DDR_VREF1_502-PadP6)") (class "Default")
      (node (ref "U6") (pin "P6") (pinfunction "PS_DDR_VREF1_502_P6") (pintype "passive"))
    )
    (net (code "225") (name "unconnected-(U6-PS_DDR_VRN_502-PadG5)") (class "Default")
      (node (ref "U6") (pin "G5") (pinfunction "PS_DDR_VRN_502_G5") (pintype "passive"))
    )
    (net (code "226") (name "unconnected-(U6-PS_DDR_VRP_502-PadH5)") (class "Default")
      (node (ref "U6") (pin "H5") (pinfunction "PS_DDR_VRP_502_H5") (pintype "passive"))
    )
    (net (code "227") (name "unconnected-(U6-PS_MIO0_500-PadE6)") (class "Default")
      (node (ref "U6") (pin "E6") (pinfunction "PS_MIO0_500_E6") (pintype "passive"))
    )
    (net (code "228") (name "unconnected-(U6-PS_MIO1_500-PadA7)") (class "Default")
      (node (ref "U6") (pin "A7") (pinfunction "PS_MIO1_500_A7") (pintype "passive"))
    )
    (net (code "229") (name "unconnected-(U6-PS_MIO2_500-PadB8)") (class "Default")
      (node (ref "U6") (pin "B8") (pinfunction "PS_MIO2_500_B8") (pintype "passive"))
    )
    (net (code "230") (name "unconnected-(U6-PS_MIO3_500-PadD6)") (class "Default")
      (node (ref "U6") (pin "D6") (pinfunction "PS_MIO3_500_D6") (pintype "passive"))
    )
    (net (code "231") (name "unconnected-(U6-PS_MIO4_500-PadB7)") (class "Default")
      (node (ref "U6") (pin "B7") (pinfunction "PS_MIO4_500_B7") (pintype "passive"))
    )
    (net (code "232") (name "unconnected-(U6-PS_MIO5_500-PadA6)") (class "Default")
      (node (ref "U6") (pin "A6") (pinfunction "PS_MIO5_500_A6") (pintype "passive"))
    )
    (net (code "233") (name "unconnected-(U6-PS_MIO6_500-PadA5)") (class "Default")
      (node (ref "U6") (pin "A5") (pinfunction "PS_MIO6_500_A5") (pintype "passive"))
    )
    (net (code "234") (name "unconnected-(U6-PS_MIO7_500-PadD8)") (class "Default")
      (node (ref "U6") (pin "D8") (pinfunction "PS_MIO7_500_D8") (pintype "passive"))
    )
    (net (code "235") (name "unconnected-(U6-PS_MIO8_500-PadD5)") (class "Default")
      (node (ref "U6") (pin "D5") (pinfunction "PS_MIO8_500_D5") (pintype "passive"))
    )
    (net (code "236") (name "unconnected-(U6-PS_MIO9_500-PadB5)") (class "Default")
      (node (ref "U6") (pin "B5") (pinfunction "PS_MIO9_500_B5") (pintype "passive"))
    )
    (net (code "237") (name "unconnected-(U6-PS_MIO10_500-PadE9)") (class "Default")
      (node (ref "U6") (pin "E9") (pinfunction "PS_MIO10_500_E9") (pintype "passive"))
    )
    (net (code "238") (name "unconnected-(U6-PS_MIO11_500-PadC6)") (class "Default")
      (node (ref "U6") (pin "C6") (pinfunction "PS_MIO11_500_C6") (pintype "passive"))
    )
    (net (code "239") (name "unconnected-(U6-PS_MIO12_500-PadD9)") (class "Default")
      (node (ref "U6") (pin "D9") (pinfunction "PS_MIO12_500_D9") (pintype "passive"))
    )
    (net (code "240") (name "unconnected-(U6-PS_MIO13_500-PadE8)") (class "Default")
      (node (ref "U6") (pin "E8") (pinfunction "PS_MIO13_500_E8") (pintype "passive"))
    )
    (net (code "241") (name "unconnected-(U6-PS_MIO14_500-PadC5)") (class "Default")
      (node (ref "U6") (pin "C5") (pinfunction "PS_MIO14_500_C5") (pintype "passive"))
    )
    (net (code "242") (name "unconnected-(U6-PS_MIO15_500-PadC8)") (class "Default")
      (node (ref "U6") (pin "C8") (pinfunction "PS_MIO15_500_C8") (pintype "passive"))
    )
    (net (code "243") (name "unconnected-(U6-PS_MIO16_501-PadA19)") (class "Default")
      (node (ref "U6") (pin "A19") (pinfunction "PS_MIO16_501_A19") (pintype "passive"))
    )
    (net (code "244") (name "unconnected-(U6-PS_MIO17_501-PadE14)") (class "Default")
      (node (ref "U6") (pin "E14") (pinfunction "PS_MIO17_501_E14") (pintype "passive"))
    )
    (net (code "245") (name "unconnected-(U6-PS_MIO18_501-PadB18)") (class "Default")
      (node (ref "U6") (pin "B18") (pinfunction "PS_MIO18_501_B18") (pintype "passive"))
    )
    (net (code "246") (name "unconnected-(U6-PS_MIO19_501-PadD10)") (class "Default")
      (node (ref "U6") (pin "D10") (pinfunction "PS_MIO19_501_D10") (pintype "passive"))
    )
    (net (code "247") (name "unconnected-(U6-PS_MIO20_501-PadA17)") (class "Default")
      (node (ref "U6") (pin "A17") (pinfunction "PS_MIO20_501_A17") (pintype "passive"))
    )
    (net (code "248") (name "unconnected-(U6-PS_MIO21_501-PadF14)") (class "Default")
      (node (ref "U6") (pin "F14") (pinfunction "PS_MIO21_501_F14") (pintype "passive"))
    )
    (net (code "249") (name "unconnected-(U6-PS_MIO22_501-PadB17)") (class "Default")
      (node (ref "U6") (pin "B17") (pinfunction "PS_MIO22_501_B17") (pintype "passive"))
    )
    (net (code "250") (name "unconnected-(U6-PS_MIO23_501-PadD11)") (class "Default")
      (node (ref "U6") (pin "D11") (pinfunction "PS_MIO23_501_D11") (pintype "passive"))
    )
    (net (code "251") (name "unconnected-(U6-PS_MIO24_501-PadA16)") (class "Default")
      (node (ref "U6") (pin "A16") (pinfunction "PS_MIO24_501_A16") (pintype "passive"))
    )
    (net (code "252") (name "unconnected-(U6-PS_MIO25_501-PadF15)") (class "Default")
      (node (ref "U6") (pin "F15") (pinfunction "PS_MIO25_501_F15") (pintype "passive"))
    )
    (net (code "253") (name "unconnected-(U6-PS_MIO26_501-PadA15)") (class "Default")
      (node (ref "U6") (pin "A15") (pinfunction "PS_MIO26_501_A15") (pintype "passive"))
    )
    (net (code "254") (name "unconnected-(U6-PS_MIO27_501-PadD13)") (class "Default")
      (node (ref "U6") (pin "D13") (pinfunction "PS_MIO27_501_D13") (pintype "passive"))
    )
    (net (code "255") (name "unconnected-(U6-PS_MIO28_501-PadC16)") (class "Default")
      (node (ref "U6") (pin "C16") (pinfunction "PS_MIO28_501_C16") (pintype "passive"))
    )
    (net (code "256") (name "unconnected-(U6-PS_MIO29_501-PadC13)") (class "Default")
      (node (ref "U6") (pin "C13") (pinfunction "PS_MIO29_501_C13") (pintype "passive"))
    )
    (net (code "257") (name "unconnected-(U6-PS_MIO30_501-PadC15)") (class "Default")
      (node (ref "U6") (pin "C15") (pinfunction "PS_MIO30_501_C15") (pintype "passive"))
    )
    (net (code "258") (name "unconnected-(U6-PS_MIO31_501-PadE16)") (class "Default")
      (node (ref "U6") (pin "E16") (pinfunction "PS_MIO31_501_E16") (pintype "passive"))
    )
    (net (code "259") (name "unconnected-(U6-PS_MIO32_501-PadA14)") (class "Default")
      (node (ref "U6") (pin "A14") (pinfunction "PS_MIO32_501_A14") (pintype "passive"))
    )
    (net (code "260") (name "unconnected-(U6-PS_MIO33_501-PadD15)") (class "Default")
      (node (ref "U6") (pin "D15") (pinfunction "PS_MIO33_501_D15") (pintype "passive"))
    )
    (net (code "261") (name "unconnected-(U6-PS_MIO34_501-PadA12)") (class "Default")
      (node (ref "U6") (pin "A12") (pinfunction "PS_MIO34_501_A12") (pintype "passive"))
    )
    (net (code "262") (name "unconnected-(U6-PS_MIO35_501-PadF12)") (class "Default")
      (node (ref "U6") (pin "F12") (pinfunction "PS_MIO35_501_F12") (pintype "passive"))
    )
    (net (code "263") (name "unconnected-(U6-PS_MIO36_501-PadA11)") (class "Default")
      (node (ref "U6") (pin "A11") (pinfunction "PS_MIO36_501_A11") (pintype "passive"))
    )
    (net (code "264") (name "unconnected-(U6-PS_MIO37_501-PadA10)") (class "Default")
      (node (ref "U6") (pin "A10") (pinfunction "PS_MIO37_501_A10") (pintype "passive"))
    )
    (net (code "265") (name "unconnected-(U6-PS_MIO38_501-PadE13)") (class "Default")
      (node (ref "U6") (pin "E13") (pinfunction "PS_MIO38_501_E13") (pintype "passive"))
    )
    (net (code "266") (name "unconnected-(U6-PS_MIO39_501-PadC18)") (class "Default")
      (node (ref "U6") (pin "C18") (pinfunction "PS_MIO39_501_C18") (pintype "passive"))
    )
    (net (code "267") (name "unconnected-(U6-PS_MIO40_501-PadD14)") (class "Default")
      (node (ref "U6") (pin "D14") (pinfunction "PS_MIO40_501_D14") (pintype "passive"))
    )
    (net (code "268") (name "unconnected-(U6-PS_MIO41_501-PadC17)") (class "Default")
      (node (ref "U6") (pin "C17") (pinfunction "PS_MIO41_501_C17") (pintype "passive"))
    )
    (net (code "269") (name "unconnected-(U6-PS_MIO42_501-PadE12)") (class "Default")
      (node (ref "U6") (pin "E12") (pinfunction "PS_MIO42_501_E12") (pintype "passive"))
    )
    (net (code "270") (name "unconnected-(U6-PS_MIO43_501-PadA9)") (class "Default")
      (node (ref "U6") (pin "A9") (pinfunction "PS_MIO43_501_A9") (pintype "passive"))
    )
    (net (code "271") (name "unconnected-(U6-PS_MIO44_501-PadF13)") (class "Default")
      (node (ref "U6") (pin "F13") (pinfunction "PS_MIO44_501_F13") (pintype "passive"))
    )
    (net (code "272") (name "unconnected-(U6-PS_MIO45_501-PadB15)") (class "Default")
      (node (ref "U6") (pin "B15") (pinfunction "PS_MIO45_501_B15") (pintype "passive"))
    )
    (net (code "273") (name "unconnected-(U6-PS_MIO46_501-PadD16)") (class "Default")
      (node (ref "U6") (pin "D16") (pinfunction "PS_MIO46_501_D16") (pintype "passive"))
    )
    (net (code "274") (name "unconnected-(U6-PS_MIO47_501-PadB14)") (class "Default")
      (node (ref "U6") (pin "B14") (pinfunction "PS_MIO47_501_B14") (pintype "passive"))
    )
    (net (code "275") (name "unconnected-(U6-PS_MIO48_501-PadB12)") (class "Default")
      (node (ref "U6") (pin "B12") (pinfunction "PS_MIO48_501_B12") (pintype "passive"))
    )
    (net (code "276") (name "unconnected-(U6-PS_MIO49_501-PadC12)") (class "Default")
      (node (ref "U6") (pin "C12") (pinfunction "PS_MIO49_501_C12") (pintype "passive"))
    )
    (net (code "277") (name "unconnected-(U6-PS_MIO50_501-PadB13)") (class "Default")
      (node (ref "U6") (pin "B13") (pinfunction "PS_MIO50_501_B13") (pintype "passive"))
    )
    (net (code "278") (name "unconnected-(U6-PS_MIO51_501-PadB9)") (class "Default")
      (node (ref "U6") (pin "B9") (pinfunction "PS_MIO51_501_B9") (pintype "passive"))
    )
    (net (code "279") (name "unconnected-(U6-PS_MIO52_501-PadC10)") (class "Default")
      (node (ref "U6") (pin "C10") (pinfunction "PS_MIO52_501_C10") (pintype "passive"))
    )
    (net (code "280") (name "unconnected-(U6-PS_MIO53_501-PadC11)") (class "Default")
      (node (ref "U6") (pin "C11") (pinfunction "PS_MIO53_501_C11") (pintype "passive"))
    )
    (net (code "281") (name "unconnected-(U6-PS_MIO_VREF_501-PadE11)") (class "Default")
      (node (ref "U6") (pin "E11") (pinfunction "PS_MIO_VREF_501_E11") (pintype "passive"))
    )
    (net (code "282") (name "unconnected-(U6-PS_SRST_B_501-PadB10)") (class "Default")
      (node (ref "U6") (pin "B10") (pinfunction "PS_SRST_B_501_B10") (pintype "passive"))
    )
    (net (code "283") (name "unconnected-(U6-RSVDGND-PadF10)") (class "Default")
      (node (ref "U6") (pin "F10") (pinfunction "RSVDGND_F10") (pintype "passive"))
    )
    (net (code "284") (name "unconnected-(U6-RSVDVCC1-PadT6)") (class "Default")
      (node (ref "U6") (pin "T6") (pinfunction "RSVDVCC1_T6") (pintype "passive"))
    )
    (net (code "285") (name "unconnected-(U6-RSVDVCC2-PadR6)") (class "Default")
      (node (ref "U6") (pin "R6") (pinfunction "RSVDVCC2_R6") (pintype "passive"))
    )
    (net (code "286") (name "unconnected-(U6-RSVDVCC3-PadN6)") (class "Default")
      (node (ref "U6") (pin "N6") (pinfunction "RSVDVCC3_N6") (pintype "passive"))
    )
    (net (code "287") (name "unconnected-(U6-VCCBATT_0-PadF11)") (class "Default")
      (node (ref "U6") (pin "F11") (pinfunction "VCCBATT_0_F11") (pintype "passive"))
    )
    (net (code "288") (name "unconnected-(U6-VCCBRAM_1-PadG11)") (class "Default")
      (node (ref "U6") (pin "G11") (pinfunction "VCCBRAM_1_G11") (pintype "passive"))
    )
    (net (code "289") (name "unconnected-(U6-VCCBRAM_2-PadH10)") (class "Default")
      (node (ref "U6") (pin "H10") (pinfunction "VCCBRAM_2_H10") (pintype "passive"))
    )
    (net (code "290") (name "unconnected-(U6-VCCPLL-PadG8)") (class "Default")
      (node (ref "U6") (pin "G8") (pinfunction "VCCPLL_G8") (pintype "passive"))
    )
    (net (code "291") (name "unconnected-(U7A-NC-PadJ1)") (class "Default")
      (node (ref "U7") (pin "J1") (pinfunction "NC_J1") (pintype "passive"))
    )
    (net (code "292") (name "unconnected-(U7A-NC-PadJ9)") (class "Default")
      (node (ref "U7") (pin "J9") (pinfunction "NC_J9") (pintype "passive"))
    )
    (net (code "293") (name "unconnected-(U7A-NC-PadL1)") (class "Default")
      (node (ref "U7") (pin "L1") (pinfunction "NC_L1") (pintype "passive"))
    )
    (net (code "294") (name "unconnected-(U7A-NC-PadL9)") (class "Default")
      (node (ref "U7") (pin "L9") (pinfunction "NC_L9") (pintype "passive"))
    )
    (net (code "295") (name "unconnected-(U7A-NC-PadM7)") (class "Default")
      (node (ref "U7") (pin "M7") (pinfunction "NC_M7") (pintype "passive"))
    )
  )
)
